# PM_Controller_v1p02.net
KiCad netlist of a schematic drawn in EAGLE
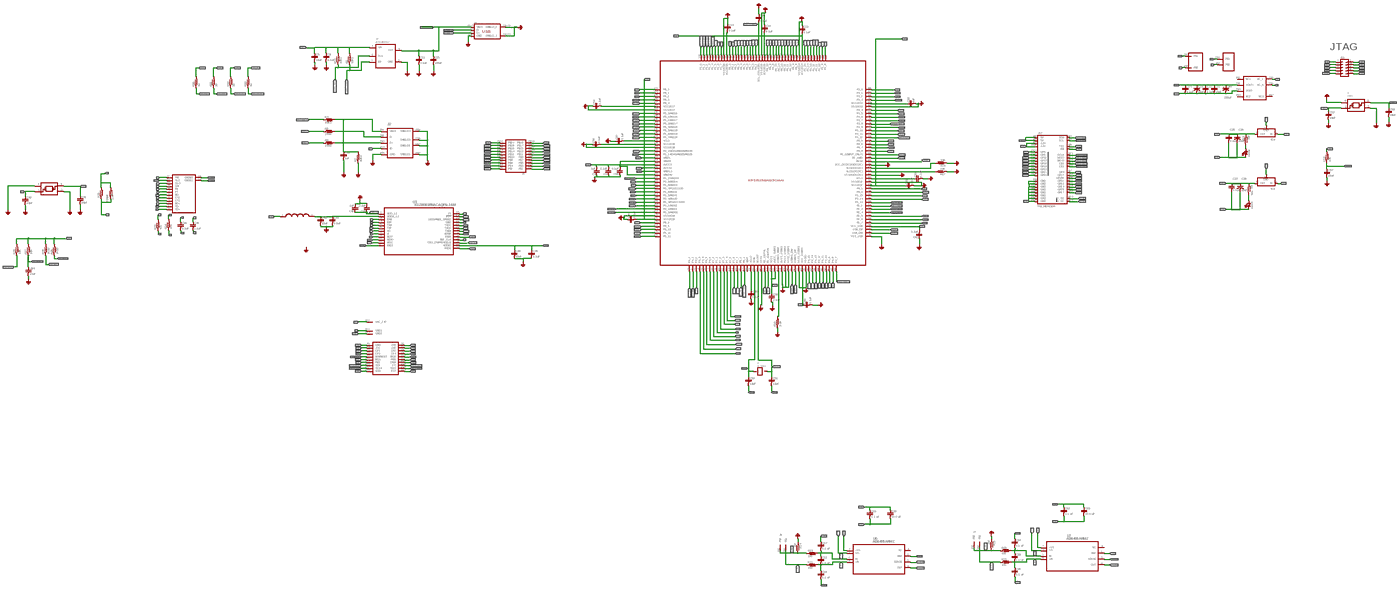
[diagram p0: schematic, sheet 1, overview]
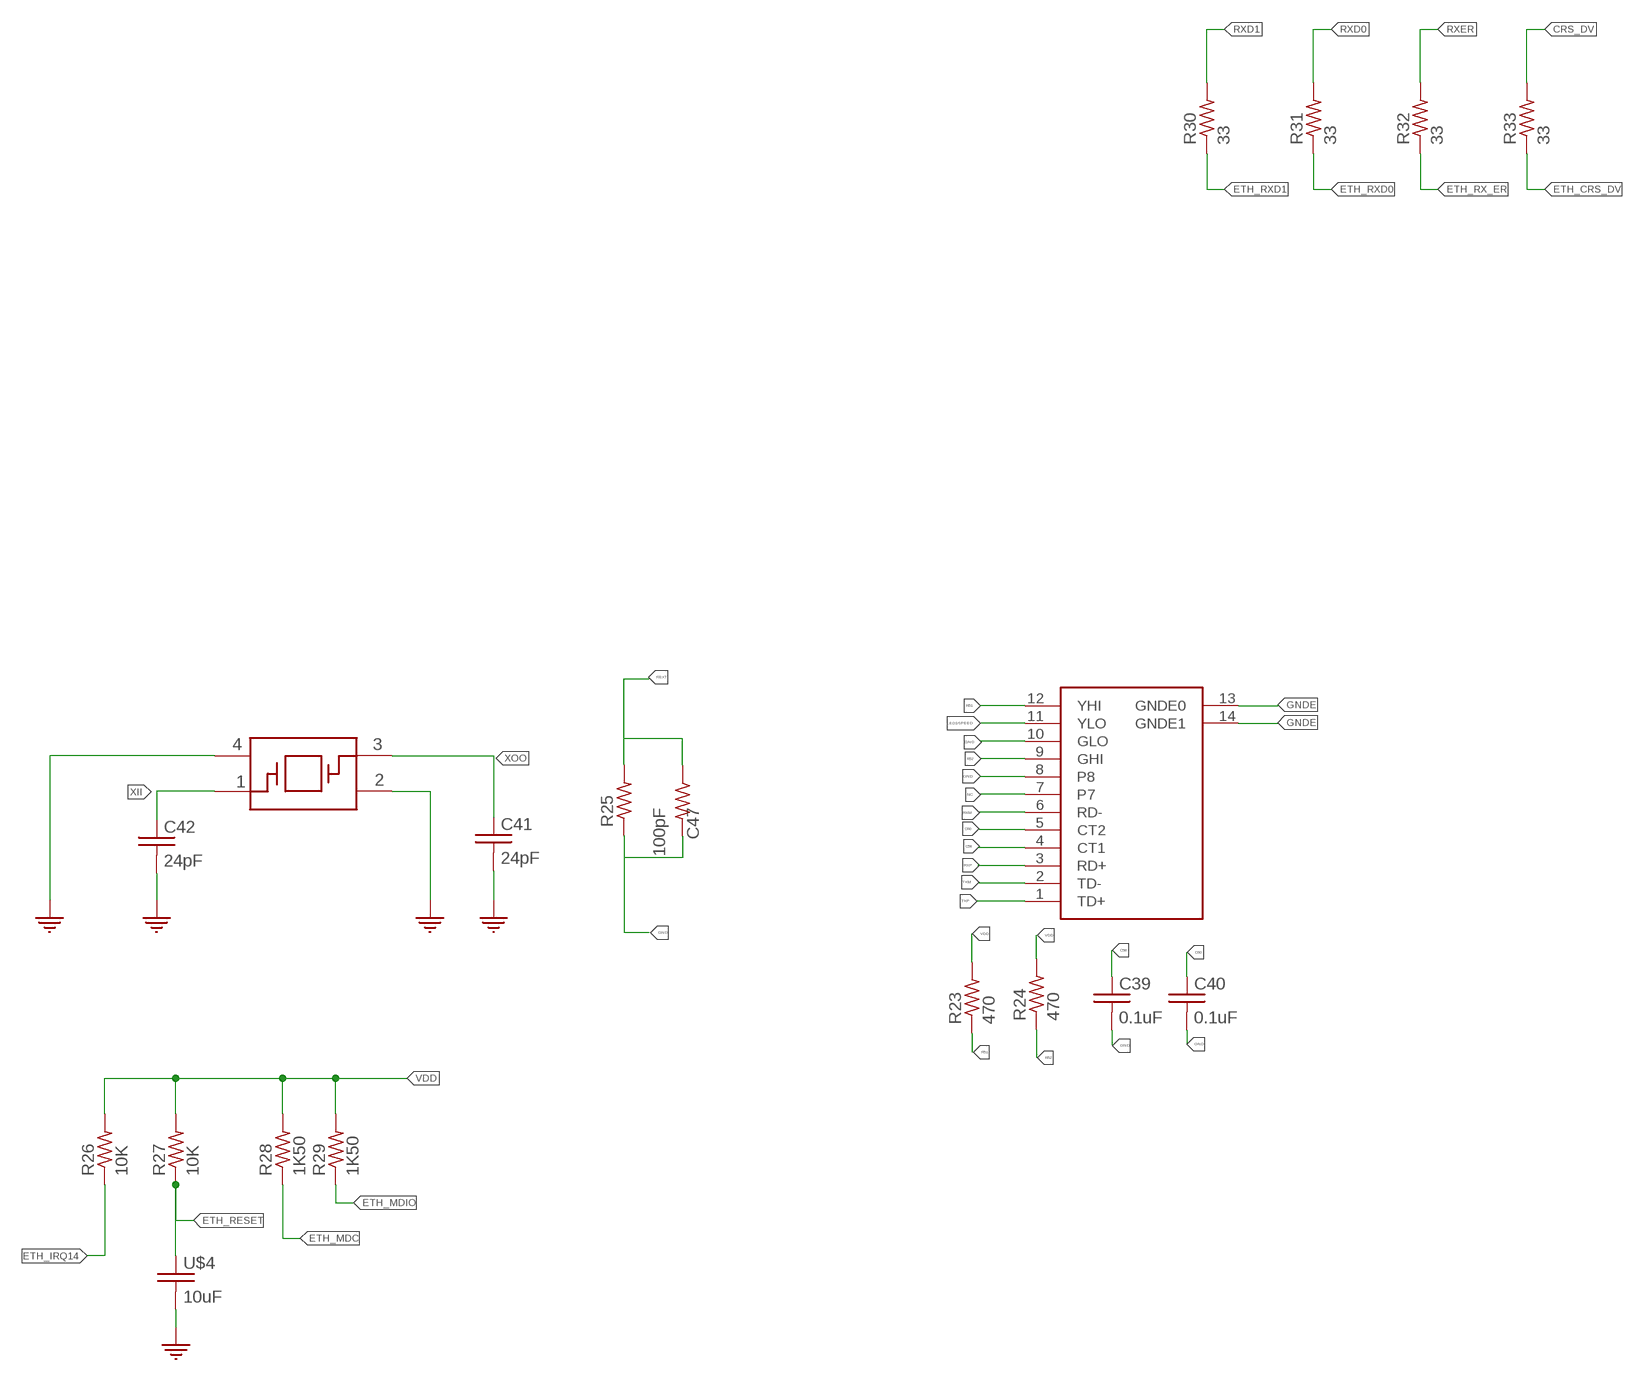
[diagram p1: schematic, sheet 1, part 1 of 6]
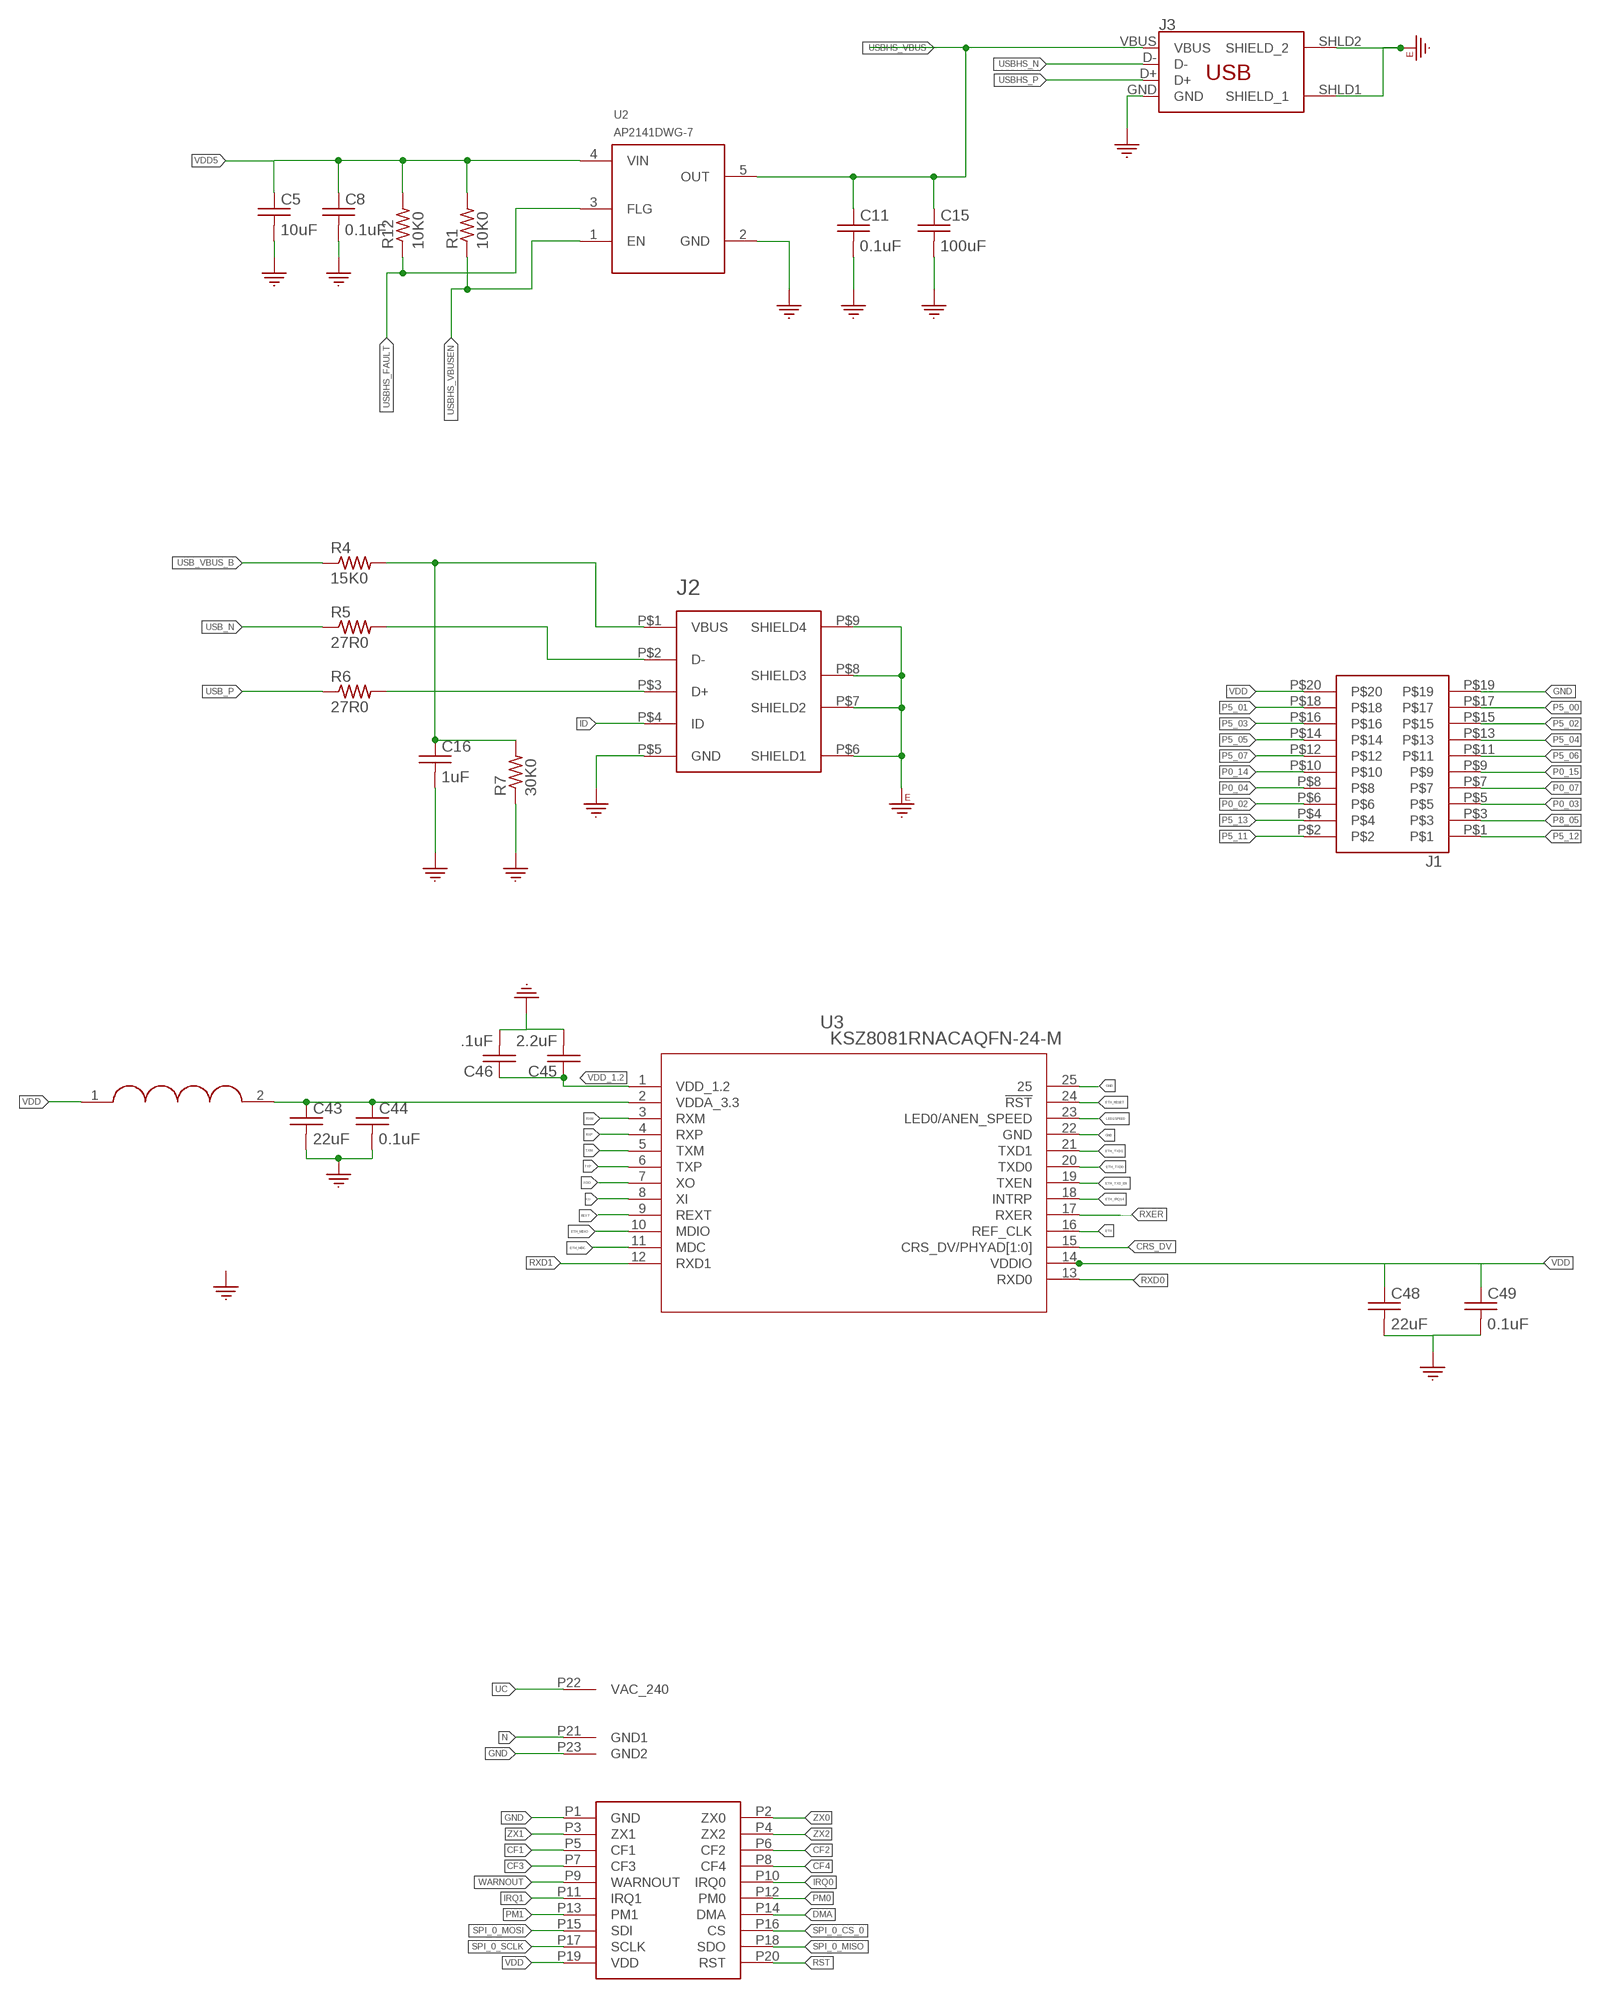
[diagram p2: schematic, sheet 1, part 2 of 6]
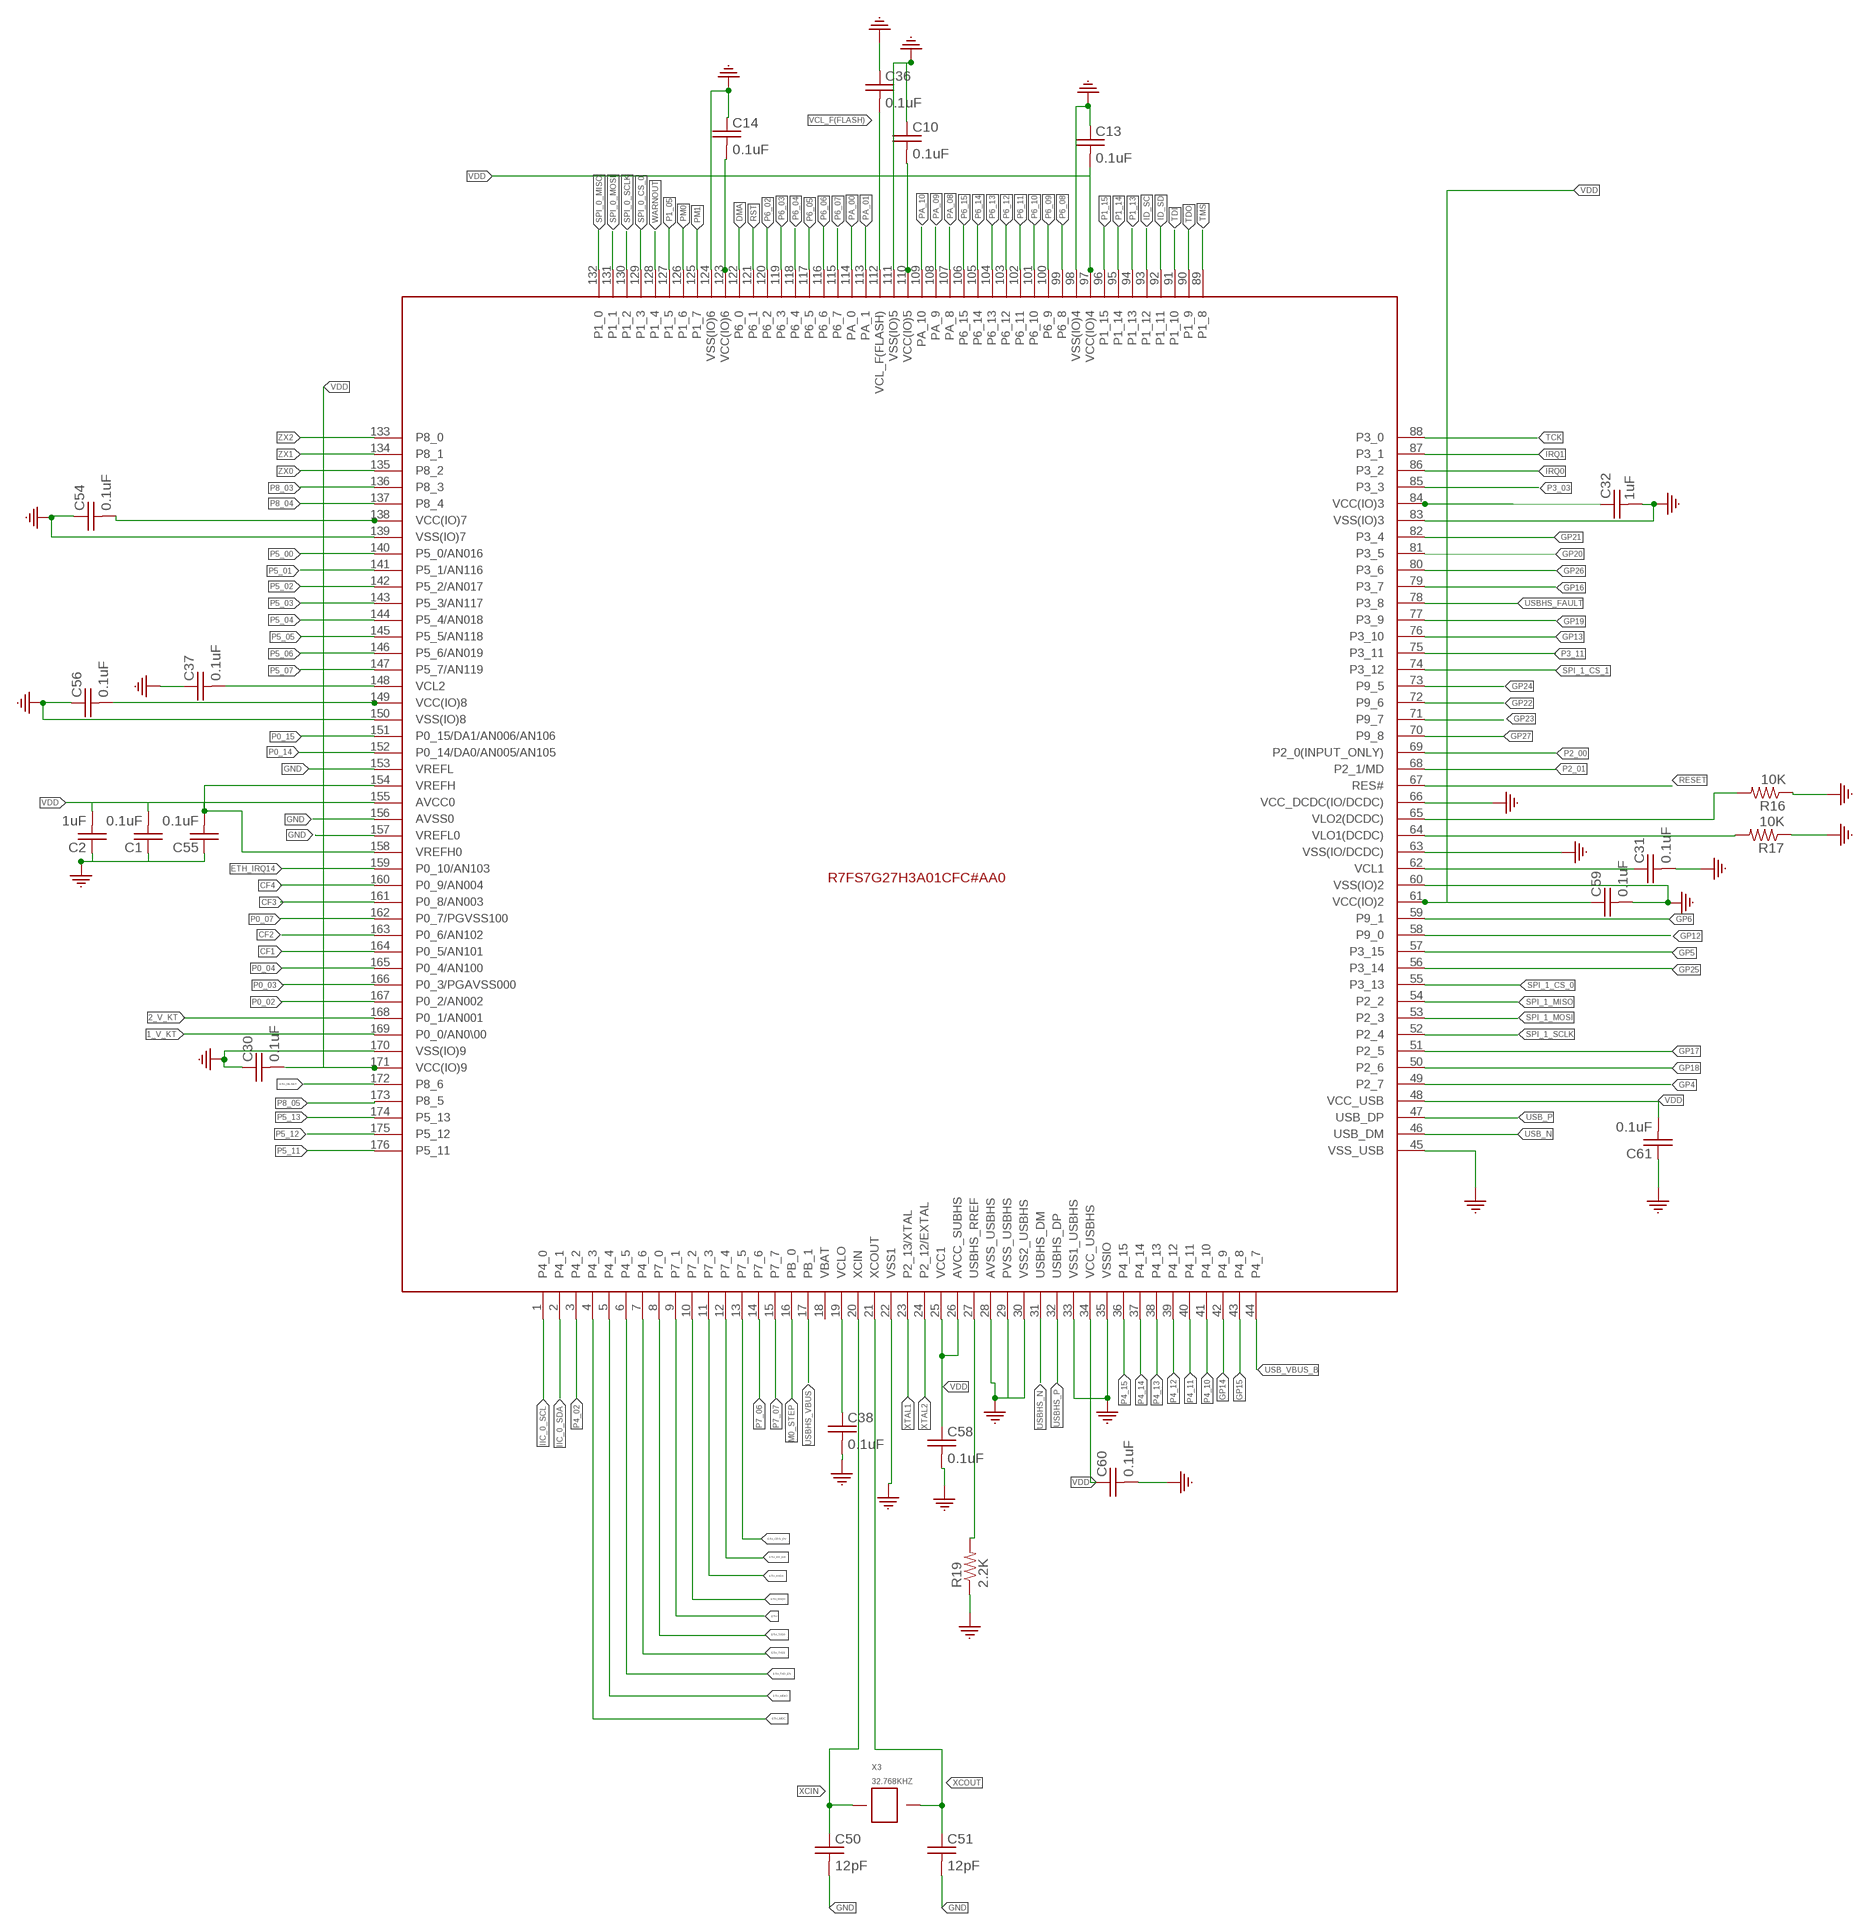
[diagram p3: schematic, sheet 1, part 3 of 6]
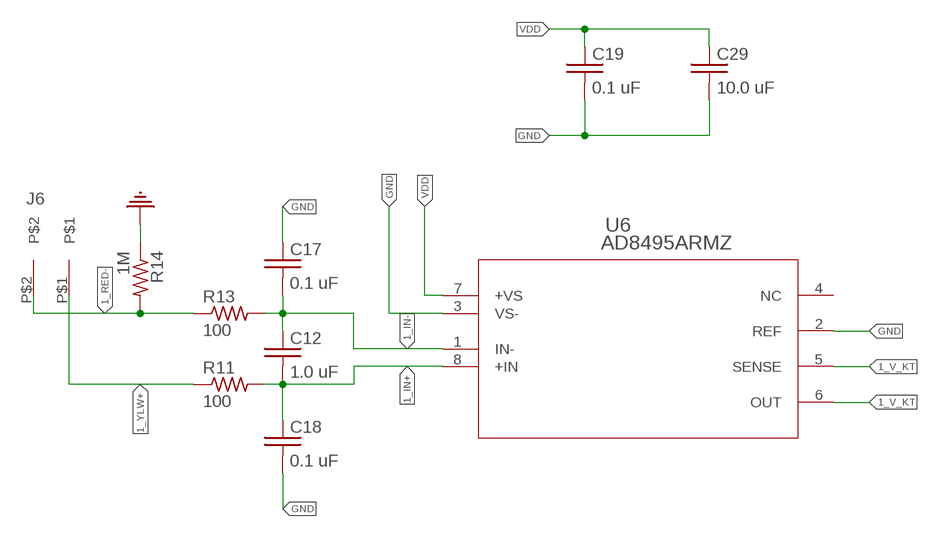
[diagram p4: schematic, sheet 1, part 4 of 6]
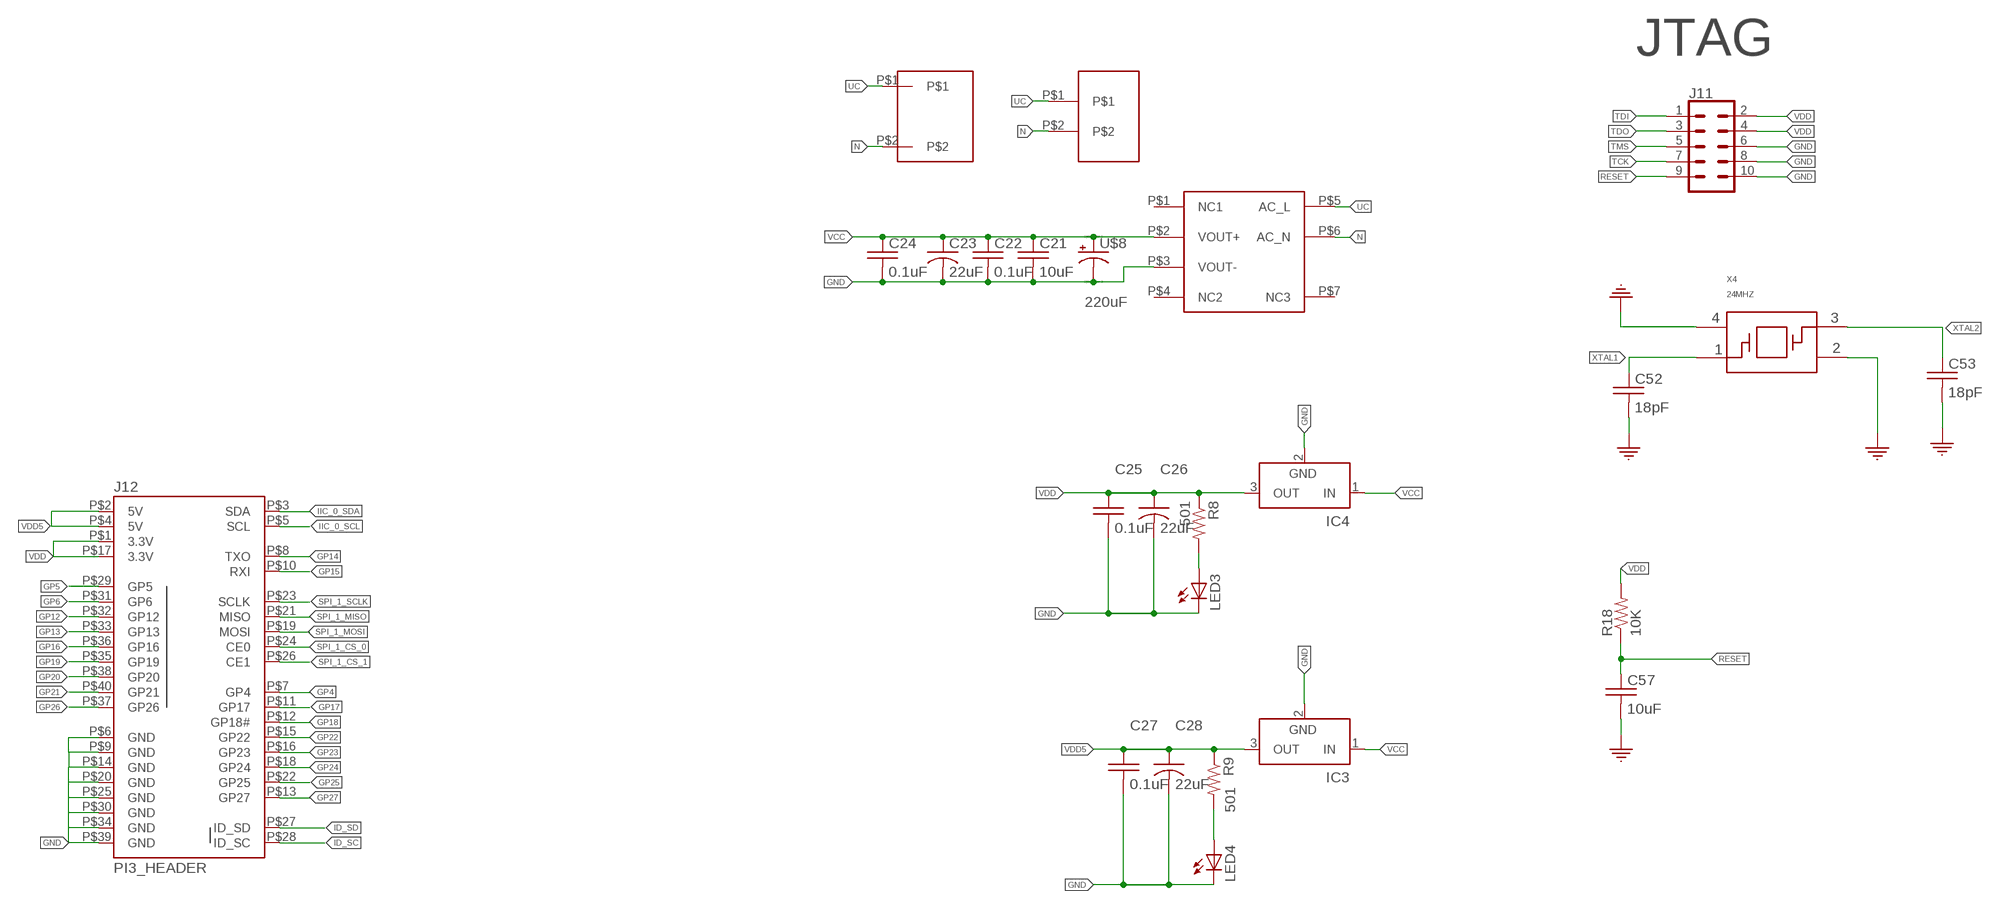
[diagram p5: schematic, sheet 1, part 5 of 6]
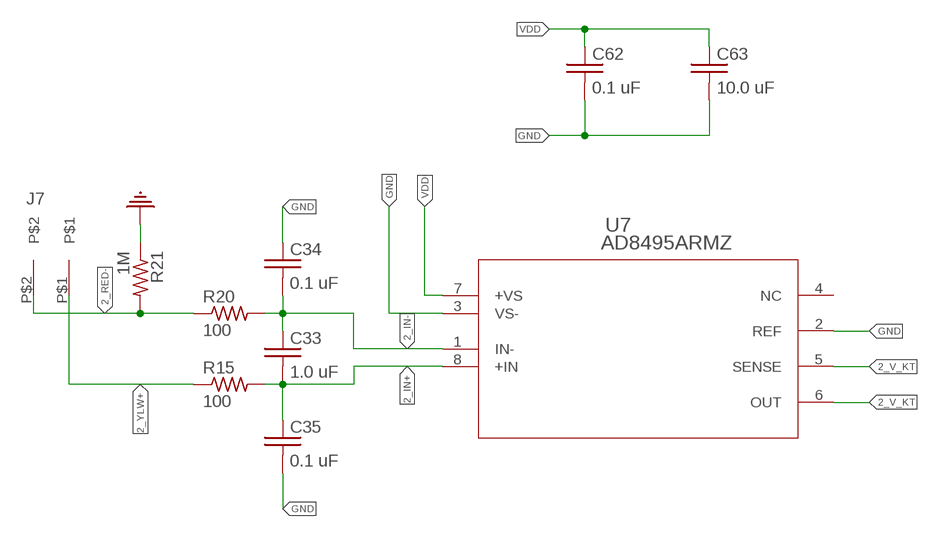
[diagram p6: schematic, sheet 1, part 6 of 6]

(export (version "E")
  (design (tool "Eeschema 10.0.6"))
  (components
    (comp (ref "C1")
      (value "0.1uF")
      (footprint "eagle-import:0402")
      (libsource (lib "eagle-import") (part "C_0402"))
    )
    (comp (ref "C2")
      (value "1uF")
      (footprint "eagle-import:0402")
      (libsource (lib "eagle-import") (part "C_0402"))
    )
    (comp (ref "C5")
      (value "10uF")
      (footprint "eagle-import:0402")
      (libsource (lib "eagle-import") (part "C_0402"))
    )
    (comp (ref "C8")
      (value "0.1uF")
      (footprint "eagle-import:0402")
      (libsource (lib "eagle-import") (part "C_0402"))
    )
    (comp (ref "C10")
      (value "0.1uF")
      (footprint "eagle-import:0402")
      (libsource (lib "eagle-import") (part "C_0402"))
    )
    (comp (ref "C11")
      (value "0.1uF")
      (footprint "eagle-import:0402")
      (libsource (lib "eagle-import") (part "C_0402"))
    )
    (comp (ref "C12")
      (value "1.0 uF")
      (footprint "eagle-import:0402")
      (libsource (lib "eagle-import") (part "C_0402"))
    )
    (comp (ref "C13")
      (value "0.1uF")
      (footprint "eagle-import:0402")
      (libsource (lib "eagle-import") (part "C_0402"))
    )
    (comp (ref "C14")
      (value "0.1uF")
      (footprint "eagle-import:0402")
      (libsource (lib "eagle-import") (part "C_0402"))
    )
    (comp (ref "C15")
      (value "100uF")
      (footprint "eagle-import:C1210")
      (libsource (lib "eagle-import") (part "C_1210"))
    )
    (comp (ref "C16")
      (value "1uF")
      (footprint "eagle-import:0402")
      (libsource (lib "eagle-import") (part "C_0402"))
    )
    (comp (ref "C17")
      (value "0.1 uF")
      (footprint "eagle-import:0402")
      (libsource (lib "eagle-import") (part "C_0402"))
    )
    (comp (ref "C18")
      (value "0.1 uF")
      (footprint "eagle-import:0402")
      (libsource (lib "eagle-import") (part "C_0402"))
    )
    (comp (ref "C19")
      (value "0.1 uF")
      (footprint "eagle-import:0402")
      (libsource (lib "eagle-import") (part "C_0402"))
    )
    (comp (ref "C20")
      (value "CAP_THIN_FILM_TDK_32922CAP")
      (footprint "eagle-import:CAP_THIN_FILM_32922")
      (libsource (lib "eagle-import") (part "CAP_THIN_FILM_TDK_32922CAP"))
    )
    (comp (ref "C21")
      (value "10uF")
      (footprint "eagle-import:0402")
      (libsource (lib "eagle-import") (part "C_0402"))
    )
    (comp (ref "C22")
      (value "0.1uF")
      (footprint "eagle-import:0402")
      (libsource (lib "eagle-import") (part "C_0402"))
    )
    (comp (ref "C23")
      (value "22uF")
      (footprint "eagle-import:C1206")
      (libsource (lib "eagle-import") (part "C-USC1206"))
    )
    (comp (ref "C24")
      (value "0.1uF")
      (footprint "eagle-import:0402")
      (libsource (lib "eagle-import") (part "C_0402"))
    )
    (comp (ref "C25")
      (value "0.1uF")
      (footprint "eagle-import:0402")
      (libsource (lib "eagle-import") (part "C_0402"))
    )
    (comp (ref "C26")
      (value "22uF")
      (footprint "eagle-import:C1206")
      (libsource (lib "eagle-import") (part "C-USC1206"))
    )
    (comp (ref "C27")
      (value "0.1uF")
      (footprint "eagle-import:0402")
      (libsource (lib "eagle-import") (part "C_0402"))
    )
    (comp (ref "C28")
      (value "22uF")
      (footprint "eagle-import:C1206")
      (libsource (lib "eagle-import") (part "C-USC1206"))
    )
    (comp (ref "C29")
      (value "10.0 uF")
      (footprint "eagle-import:0402")
      (libsource (lib "eagle-import") (part "C_0402"))
    )
    (comp (ref "C30")
      (value "0.1uF")
      (footprint "eagle-import:0402")
      (libsource (lib "eagle-import") (part "C_0402"))
    )
    (comp (ref "C31")
      (value "0.1uF")
      (footprint "eagle-import:0402")
      (libsource (lib "eagle-import") (part "C_0402"))
    )
    (comp (ref "C32")
      (value "1uF")
      (footprint "eagle-import:0402")
      (libsource (lib "eagle-import") (part "C_0402"))
    )
    (comp (ref "C33")
      (value "1.0 uF")
      (footprint "eagle-import:0402")
      (libsource (lib "eagle-import") (part "C_0402"))
    )
    (comp (ref "C34")
      (value "0.1 uF")
      (footprint "eagle-import:0402")
      (libsource (lib "eagle-import") (part "C_0402"))
    )
    (comp (ref "C35")
      (value "0.1 uF")
      (footprint "eagle-import:0402")
      (libsource (lib "eagle-import") (part "C_0402"))
    )
    (comp (ref "C36")
      (value "0.1uF")
      (footprint "eagle-import:0402")
      (libsource (lib "eagle-import") (part "C_0402"))
    )
    (comp (ref "C37")
      (value "0.1uF")
      (footprint "eagle-import:0402")
      (libsource (lib "eagle-import") (part "C_0402"))
    )
    (comp (ref "C38")
      (value "0.1uF")
      (footprint "eagle-import:0402")
      (libsource (lib "eagle-import") (part "C_0402"))
    )
    (comp (ref "C39")
      (value "0.1uF")
      (footprint "eagle-import:0402")
      (libsource (lib "eagle-import") (part "C_0402"))
    )
    (comp (ref "C40")
      (value "0.1uF")
      (footprint "eagle-import:0402")
      (libsource (lib "eagle-import") (part "C_0402"))
    )
    (comp (ref "C41")
      (value "24pF")
      (footprint "eagle-import:0402")
      (libsource (lib "eagle-import") (part "C_0402"))
    )
    (comp (ref "C42")
      (value "24pF")
      (footprint "eagle-import:0402")
      (libsource (lib "eagle-import") (part "C_0402"))
    )
    (comp (ref "C43")
      (value "22uF")
      (footprint "eagle-import:0603")
      (libsource (lib "eagle-import") (part "C_0603"))
    )
    (comp (ref "C44")
      (value "0.1uF")
      (footprint "eagle-import:0402")
      (libsource (lib "eagle-import") (part "C_0402"))
    )
    (comp (ref "C45")
      (value "2.2uF")
      (footprint "eagle-import:0402")
      (libsource (lib "eagle-import") (part "C_0402"))
    )
    (comp (ref "C46")
      (value ".1uF")
      (footprint "eagle-import:0402")
      (libsource (lib "eagle-import") (part "C_0402"))
    )
    (comp (ref "C47")
      (value "100pF")
      (footprint "eagle-import:0402")
      (libsource (lib "eagle-import") (part "R_0402"))
    )
    (comp (ref "C48")
      (value "22uF")
      (footprint "eagle-import:0603")
      (libsource (lib "eagle-import") (part "C_0603"))
    )
    (comp (ref "C49")
      (value "0.1uF")
      (footprint "eagle-import:0402")
      (libsource (lib "eagle-import") (part "C_0402"))
    )
    (comp (ref "C50")
      (value "12pF")
      (footprint "eagle-import:0402")
      (libsource (lib "eagle-import") (part "C_0402"))
    )
    (comp (ref "C51")
      (value "12pF")
      (footprint "eagle-import:0402")
      (libsource (lib "eagle-import") (part "C_0402"))
    )
    (comp (ref "C52")
      (value "18pF")
      (footprint "eagle-import:0402")
      (libsource (lib "eagle-import") (part "C_0402"))
    )
    (comp (ref "C53")
      (value "18pF")
      (footprint "eagle-import:0402")
      (libsource (lib "eagle-import") (part "C_0402"))
    )
    (comp (ref "C54")
      (value "0.1uF")
      (footprint "eagle-import:0402")
      (libsource (lib "eagle-import") (part "C_0402"))
    )
    (comp (ref "C55")
      (value "0.1uF")
      (footprint "eagle-import:0402")
      (libsource (lib "eagle-import") (part "C_0402"))
    )
    (comp (ref "C56")
      (value "0.1uF")
      (footprint "eagle-import:0402")
      (libsource (lib "eagle-import") (part "C_0402"))
    )
    (comp (ref "C57")
      (value "10uF")
      (footprint "eagle-import:0402")
      (libsource (lib "eagle-import") (part "C_0402"))
    )
    (comp (ref "C58")
      (value "0.1uF")
      (footprint "eagle-import:0402")
      (libsource (lib "eagle-import") (part "C_0402"))
    )
    (comp (ref "C59")
      (value "0.1uF")
      (footprint "eagle-import:0402")
      (libsource (lib "eagle-import") (part "C_0402"))
    )
    (comp (ref "C60")
      (value "0.1uF")
      (footprint "eagle-import:0402")
      (libsource (lib "eagle-import") (part "C_0402"))
    )
    (comp (ref "C61")
      (value "0.1uF")
      (footprint "eagle-import:0402")
      (libsource (lib "eagle-import") (part "C_0402"))
    )
    (comp (ref "C62")
      (value "0.1 uF")
      (footprint "eagle-import:0402")
      (libsource (lib "eagle-import") (part "C_0402"))
    )
    (comp (ref "C63")
      (value "10.0 uF")
      (footprint "eagle-import:0402")
      (libsource (lib "eagle-import") (part "C_0402"))
    )
    (comp (ref "FB2/2")
      (value "FB_0805_120_OHM")
      (footprint "eagle-import:0805")
      (libsource (lib "eagle-import") (part "FB_0805_120_OHM"))
    )
    (comp (ref "IC3")
      (value "LT1129CST5")
      (footprint "eagle-import:SOT223")
      (fields (field (name "MPN") "LT1129CST-5#PBF"))
      (libsource (lib "eagle-import") (part "LT1129CST5"))
    )
    (comp (ref "IC4")
      (value "LT1129CST3")
      (footprint "eagle-import:SOT223")
      (fields (field (name "MPN") "LT1129CST-5#PBF"))
      (libsource (lib "eagle-import") (part "LT1129CST3"))
    )
    (comp (ref "J1")
      (value "2_X_10_HEADER_GENERIC")
      (footprint "eagle-import:2_X_10_.1_INCH")
      (libsource (lib "eagle-import") (part "2_X_10_HEADER_GENERIC"))
    )
    (comp (ref "J2")
      (value "USB_MICRO-B")
      (footprint "eagle-import:USB_MICRO-B")
      (libsource (lib "eagle-import") (part "USB_MICRO-B"))
    )
    (comp (ref "J3")
      (value "USB_A")
      (footprint "eagle-import:USB_A_SMT")
      (libsource (lib "eagle-import") (part "USB_A"))
    )
    (comp (ref "J4")
      (value "RJ45_WITH_ELEC")
      (footprint "eagle-import:RJ45_TH_ELEC")
      (libsource (lib "eagle-import") (part "RJ45_WITH_ELEC"))
    )
    (comp (ref "J6")
      (value "3.81MM_1_X_2_RT_ANGLE_PLUG_HEADER")
      (footprint "eagle-import:2_3.81MM_PITCH")
      (libsource (lib "eagle-import") (part "3.81MM_1_X_2_RT_ANGLE_PLUG_HEADER"))
    )
    (comp (ref "J7")
      (value "3.81MM_1_X_2_RT_ANGLE_PLUG_HEADER")
      (footprint "eagle-import:2_3.81MM_PITCH")
      (libsource (lib "eagle-import") (part "3.81MM_1_X_2_RT_ANGLE_PLUG_HEADER"))
    )
    (comp (ref "J11")
      (value "CONN_05X2PTH")
      (footprint "eagle-import:2X5")
      (libsource (lib "eagle-import") (part "CONN_05X2PTH"))
    )
    (comp (ref "J12")
      (value "PI3_HEADER")
      (footprint "eagle-import:HEADER_2_X_20_.1_INCH")
      (libsource (lib "eagle-import") (part "PI3_HEADER"))
    )
    (comp (ref "LED3")
      (value "LED_0805_GREEN")
      (footprint "eagle-import:LED_0805_GREEN")
      (libsource (lib "eagle-import") (part "LED_0805_GREEN"))
    )
    (comp (ref "LED4")
      (value "LED_0805_GREEN")
      (footprint "eagle-import:LED_0805_GREEN")
      (libsource (lib "eagle-import") (part "LED_0805_GREEN"))
    )
    (comp (ref "R1")
      (value "10K0")
      (footprint "eagle-import:0402")
      (libsource (lib "eagle-import") (part "R_0402"))
    )
    (comp (ref "R4")
      (value "15K0")
      (footprint "eagle-import:0402")
      (libsource (lib "eagle-import") (part "R_0402"))
    )
    (comp (ref "R5")
      (value "27R0")
      (footprint "eagle-import:0402")
      (libsource (lib "eagle-import") (part "R_0402"))
    )
    (comp (ref "R6")
      (value "27R0")
      (footprint "eagle-import:0402")
      (libsource (lib "eagle-import") (part "R_0402"))
    )
    (comp (ref "R7")
      (value "30K0")
      (footprint "eagle-import:0402")
      (libsource (lib "eagle-import") (part "R_0402"))
    )
    (comp (ref "R8")
      (value "501")
      (footprint "eagle-import:0402")
      (libsource (lib "eagle-import") (part "R_0402"))
    )
    (comp (ref "R9")
      (value "501")
      (footprint "eagle-import:0402")
      (libsource (lib "eagle-import") (part "R_0402"))
    )
    (comp (ref "R11")
      (value "100")
      (footprint "eagle-import:0402")
      (libsource (lib "eagle-import") (part "R_0402"))
    )
    (comp (ref "R12")
      (value "10K0")
      (footprint "eagle-import:0402")
      (libsource (lib "eagle-import") (part "R_0402"))
    )
    (comp (ref "R13")
      (value "100")
      (footprint "eagle-import:0402")
      (libsource (lib "eagle-import") (part "R_0402"))
    )
    (comp (ref "R14")
      (value "1M")
      (footprint "eagle-import:0402")
      (libsource (lib "eagle-import") (part "R_0402"))
    )
    (comp (ref "R15")
      (value "100")
      (footprint "eagle-import:0402")
      (libsource (lib "eagle-import") (part "R_0402"))
    )
    (comp (ref "R16")
      (value "10K")
      (footprint "eagle-import:0402")
      (libsource (lib "eagle-import") (part "R_0402"))
    )
    (comp (ref "R17")
      (value "10K")
      (footprint "eagle-import:0402")
      (libsource (lib "eagle-import") (part "R_0402"))
    )
    (comp (ref "R18")
      (value "10K")
      (footprint "eagle-import:0402")
      (libsource (lib "eagle-import") (part "R_0402"))
    )
    (comp (ref "R19")
      (value "2.2K")
      (footprint "eagle-import:0402")
      (libsource (lib "eagle-import") (part "R_0402"))
    )
    (comp (ref "R20")
      (value "100")
      (footprint "eagle-import:0402")
      (libsource (lib "eagle-import") (part "R_0402"))
    )
    (comp (ref "R21")
      (value "1M")
      (footprint "eagle-import:0402")
      (libsource (lib "eagle-import") (part "R_0402"))
    )
    (comp (ref "R23")
      (value "470")
      (footprint "eagle-import:0402")
      (libsource (lib "eagle-import") (part "R_0402"))
    )
    (comp (ref "R24")
      (value "470")
      (footprint "eagle-import:0402")
      (libsource (lib "eagle-import") (part "R_0402"))
    )
    (comp (ref "R25")
      (value "6k49")
      (footprint "eagle-import:0402")
      (libsource (lib "eagle-import") (part "R_0402"))
    )
    (comp (ref "R26")
      (value "10K")
      (footprint "eagle-import:0402")
      (libsource (lib "eagle-import") (part "R_0402"))
    )
    (comp (ref "R27")
      (value "10K")
      (footprint "eagle-import:0402")
      (libsource (lib "eagle-import") (part "R_0402"))
    )
    (comp (ref "R28")
      (value "1K50")
      (footprint "eagle-import:0402")
      (libsource (lib "eagle-import") (part "R_0402"))
    )
    (comp (ref "R29")
      (value "1K50")
      (footprint "eagle-import:0402")
      (libsource (lib "eagle-import") (part "R_0402"))
    )
    (comp (ref "R30")
      (value "33")
      (footprint "eagle-import:0402")
      (libsource (lib "eagle-import") (part "R_0402"))
    )
    (comp (ref "R31")
      (value "33")
      (footprint "eagle-import:0402")
      (libsource (lib "eagle-import") (part "R_0402"))
    )
    (comp (ref "R32")
      (value "33")
      (footprint "eagle-import:0402")
      (libsource (lib "eagle-import") (part "R_0402"))
    )
    (comp (ref "R33")
      (value "33")
      (footprint "eagle-import:0402")
      (libsource (lib "eagle-import") (part "R_0402"))
    )
    (comp (ref "U$2")
      (value "METER_BASE")
      (footprint "eagle-import:METER_BASE")
      (libsource (lib "eagle-import") (part "METER_BASE"))
    )
    (comp (ref "U$3")
      (value "XTAL_25_MHZ")
      (footprint "eagle-import:SMD_3225")
      (libsource (lib "eagle-import") (part "XTAL_25_MHZ"))
    )
    (comp (ref "U$4")
      (value "10uF")
      (footprint "eagle-import:0402")
      (libsource (lib "eagle-import") (part "C_0402"))
    )
    (comp (ref "U$7")
      (value "VAR_10MM_VDRUS10")
      (footprint "eagle-import:VAR_10MM_VDRUS10")
      (libsource (lib "eagle-import") (part "VAR_10MM_VDRUS10"))
    )
    (comp (ref "U$8")
      (value "220uF")
      (footprint "eagle-import:C_AL_ELECTROLYTIC_SMD_220UF")
      (libsource (lib "eagle-import") (part "C_AL_ELECTROLYTIC_SMD_220UF"))
    )
    (comp (ref "U2")
      (value "AP2141DWG-5")
      (footprint "eagle-import:SOT-23-5")
      (libsource (lib "eagle-import") (part "AP2141DWG-5"))
    )
    (comp (ref "U3")
      (value "KSZ8081RNACAQFN-24-M")
      (footprint "eagle-import:QFN-24-M")
      (fields (field (name "MANUFACTURER_PART_NUMBER") "KSZ8081RNACA"))
      (libsource (lib "eagle-import") (part "KSZ8081RNACAQFN-24-M"))
    )
    (comp (ref "U4")
      (value "S7G2_X_176")
      (footprint "eagle-import:LQFP176_24X24")
      (libsource (lib "eagle-import") (part "S7G2_X_176"))
    )
    (comp (ref "U5")
      (value "TMLM_04109")
      (footprint "eagle-import:TMLM04")
      (libsource (lib "eagle-import") (part "TMLM_04109"))
    )
    (comp (ref "U6")
      (value "AD8495ARMZ")
      (footprint "eagle-import:RM_8_ADI")
      (libsource (lib "eagle-import") (part "AD8495ARMZ"))
    )
    (comp (ref "U7")
      (value "AD8495ARMZ")
      (footprint "eagle-import:RM_8_ADI")
      (libsource (lib "eagle-import") (part "AD8495ARMZ"))
    )
    (comp (ref "X3")
      (value "32.768KHZ")
      (footprint "eagle-import:SMD_X_2_PADS")
      (libsource (lib "eagle-import") (part "XTAL_32.768KHZ"))
    )
    (comp (ref "X4")
      (value "24MHZ")
      (footprint "eagle-import:SMD_3225")
      (libsource (lib "eagle-import") (part "XTAL_24_MHZ"))
    )
  )
  (nets
    (net (code "1") (name "1_IN+") (class "Default")
      (node (ref "C12") (pin "P$2") (pinfunction "2_P$2") (pintype "passive"))
      (node (ref "C18") (pin "P$1") (pinfunction "1_P$1") (pintype "passive"))
      (node (ref "R11") (pin "P$2") (pinfunction "2_P$2") (pintype "passive"))
      (node (ref "U6") (pin "8") (pinfunction "+IN_8") (pintype "input"))
    )
    (net (code "2") (name "1_IN-") (class "Default")
      (node (ref "C12") (pin "P$1") (pinfunction "1_P$1") (pintype "passive"))
      (node (ref "C17") (pin "P$2") (pinfunction "2_P$2") (pintype "passive"))
      (node (ref "R13") (pin "P$2") (pinfunction "2_P$2") (pintype "passive"))
      (node (ref "U6") (pin "1") (pinfunction "IN-_1") (pintype "input"))
    )
    (net (code "3") (name "1_RED-") (class "Default")
      (node (ref "J6") (pin "P$2") (pinfunction "P$2_P$2") (pintype "bidirectional"))
      (node (ref "R13") (pin "P$1") (pinfunction "1_P$1") (pintype "passive"))
      (node (ref "R14") (pin "P$2") (pinfunction "2_P$2") (pintype "passive"))
    )
    (net (code "4") (name "1_V_KT") (class "Default")
      (node (ref "U4") (pin "169") (pinfunction "P0_0/AN0\\00_169") (pintype "bidirectional"))
      (node (ref "U6") (pin "5") (pinfunction "SENSE_5") (pintype "passive"))
      (node (ref "U6") (pin "6") (pinfunction "OUT_6") (pintype "output"))
    )
    (net (code "5") (name "1_YLW+") (class "Default")
      (node (ref "J6") (pin "P$1") (pinfunction "P$1_P$1") (pintype "bidirectional"))
      (node (ref "R11") (pin "P$1") (pinfunction "1_P$1") (pintype "passive"))
    )
    (net (code "6") (name "2_IN+") (class "Default")
      (node (ref "C33") (pin "P$2") (pinfunction "2_P$2") (pintype "passive"))
      (node (ref "C35") (pin "P$1") (pinfunction "1_P$1") (pintype "passive"))
      (node (ref "R15") (pin "P$2") (pinfunction "2_P$2") (pintype "passive"))
      (node (ref "U7") (pin "8") (pinfunction "+IN_8") (pintype "input"))
    )
    (net (code "7") (name "2_IN-") (class "Default")
      (node (ref "C33") (pin "P$1") (pinfunction "1_P$1") (pintype "passive"))
      (node (ref "C34") (pin "P$2") (pinfunction "2_P$2") (pintype "passive"))
      (node (ref "R20") (pin "P$2") (pinfunction "2_P$2") (pintype "passive"))
      (node (ref "U7") (pin "1") (pinfunction "IN-_1") (pintype "input"))
    )
    (net (code "8") (name "2_RED-") (class "Default")
      (node (ref "J7") (pin "P$2") (pinfunction "P$2_P$2") (pintype "bidirectional"))
      (node (ref "R20") (pin "P$1") (pinfunction "1_P$1") (pintype "passive"))
      (node (ref "R21") (pin "P$2") (pinfunction "2_P$2") (pintype "passive"))
    )
    (net (code "9") (name "2_V_KT") (class "Default")
      (node (ref "U4") (pin "168") (pinfunction "P0_1/AN001_168") (pintype "bidirectional"))
      (node (ref "U7") (pin "5") (pinfunction "SENSE_5") (pintype "passive"))
      (node (ref "U7") (pin "6") (pinfunction "OUT_6") (pintype "output"))
    )
    (net (code "10") (name "2_YLW+") (class "Default")
      (node (ref "J7") (pin "P$1") (pinfunction "P$1_P$1") (pintype "bidirectional"))
      (node (ref "R15") (pin "P$1") (pinfunction "1_P$1") (pintype "passive"))
    )
    (net (code "11") (name "C58") (class "Default")
      (node (ref "C39") (pin "P$1") (pinfunction "1_P$1") (pintype "passive"))
      (node (ref "J4") (pin "4") (pinfunction "CT1_4") (pintype "bidirectional"))
    )
    (net (code "12") (name "C60") (class "Default")
      (node (ref "C40") (pin "P$1") (pinfunction "1_P$1") (pintype "passive"))
      (node (ref "J4") (pin "5") (pinfunction "CT2_5") (pintype "bidirectional"))
    )
    (net (code "13") (name "CF1") (class "Default")
      (node (ref "U$2") (pin "P5") (pinfunction "CF1_P5") (pintype "bidirectional"))
      (node (ref "U4") (pin "164") (pinfunction "P0_5/AN101_164") (pintype "bidirectional"))
    )
    (net (code "14") (name "CF2") (class "Default")
      (node (ref "U$2") (pin "P6") (pinfunction "CF2_P6") (pintype "bidirectional"))
      (node (ref "U4") (pin "163") (pinfunction "P0_6/AN102_163") (pintype "bidirectional"))
    )
    (net (code "15") (name "CF3") (class "Default")
      (node (ref "U$2") (pin "P7") (pinfunction "CF3_P7") (pintype "bidirectional"))
      (node (ref "U4") (pin "161") (pinfunction "P0_8/AN003_161") (pintype "bidirectional"))
    )
    (net (code "16") (name "CF4") (class "Default")
      (node (ref "U$2") (pin "P8") (pinfunction "CF4_P8") (pintype "bidirectional"))
      (node (ref "U4") (pin "160") (pinfunction "P0_9/AN004_160") (pintype "bidirectional"))
    )
    (net (code "17") (name "CRS_DV") (class "Default")
      (node (ref "R33") (pin "P$2") (pinfunction "2_P$2") (pintype "passive"))
      (node (ref "U3") (pin "15") (pinfunction "CRS_DV/PHYAD[1:0]_15") (pintype "bidirectional"))
    )
    (net (code "18") (name "DMA") (class "Default")
      (node (ref "U$2") (pin "P14") (pinfunction "DMA_P14") (pintype "bidirectional"))
      (node (ref "U4") (pin "122") (pinfunction "P6_0_122") (pintype "bidirectional"))
    )
    (net (code "19") (name "ETH") (class "Default")
      (node (ref "U3") (pin "16") (pinfunction "REF_CLK_16") (pintype "bidirectional"))
      (node (ref "U4") (pin "9") (pinfunction "P7_1_9") (pintype "bidirectional"))
    )
    (net (code "20") (name "ETH_CRS_DV") (class "Default")
      (node (ref "R33") (pin "P$1") (pinfunction "1_P$1") (pintype "passive"))
      (node (ref "U4") (pin "13") (pinfunction "P7_5_13") (pintype "bidirectional"))
    )
    (net (code "21") (name "ETH_IRQ14") (class "Default")
      (node (ref "R26") (pin "P$1") (pinfunction "1_P$1") (pintype "passive"))
      (node (ref "U3") (pin "18") (pinfunction "INTRP_18") (pintype "bidirectional"))
      (node (ref "U4") (pin "159") (pinfunction "P0_10/AN103_159") (pintype "bidirectional"))
    )
    (net (code "22") (name "ETH_MDC") (class "Default")
      (node (ref "R28") (pin "P$1") (pinfunction "1_P$1") (pintype "passive"))
      (node (ref "U3") (pin "11") (pinfunction "MDC_11") (pintype "input"))
      (node (ref "U4") (pin "4") (pinfunction "P4_3_4") (pintype "bidirectional"))
    )
    (net (code "23") (name "ETH_MDIO") (class "Default")
      (node (ref "R29") (pin "P$1") (pinfunction "1_P$1") (pintype "passive"))
      (node (ref "U3") (pin "10") (pinfunction "MDIO_10") (pintype "bidirectional"))
      (node (ref "U4") (pin "5") (pinfunction "P4_4_5") (pintype "bidirectional"))
    )
    (net (code "24") (name "ETH_RESET") (class "Default")
      (node (ref "R27") (pin "P$1") (pinfunction "1_P$1") (pintype "passive"))
      (node (ref "U$4") (pin "P$1") (pinfunction "1_P$1") (pintype "passive"))
      (node (ref "U3") (pin "24") (pinfunction "~{RST}_24") (pintype "input"))
      (node (ref "U4") (pin "172") (pinfunction "P8_6_172") (pintype "bidirectional"))
    )
    (net (code "25") (name "ETH_RXD0") (class "Default")
      (node (ref "R31") (pin "P$1") (pinfunction "1_P$1") (pintype "passive"))
      (node (ref "U4") (pin "10") (pinfunction "P7_2_10") (pintype "bidirectional"))
    )
    (net (code "26") (name "ETH_RXD1") (class "Default")
      (node (ref "R30") (pin "P$1") (pinfunction "1_P$1") (pintype "passive"))
      (node (ref "U4") (pin "11") (pinfunction "P7_3_11") (pintype "bidirectional"))
    )
    (net (code "27") (name "ETH_RX_ER") (class "Default")
      (node (ref "R32") (pin "P$1") (pinfunction "1_P$1") (pintype "passive"))
      (node (ref "U4") (pin "12") (pinfunction "P7_4_12") (pintype "bidirectional"))
    )
    (net (code "28") (name "ETH_TXD0") (class "Default")
      (node (ref "U3") (pin "20") (pinfunction "TXD0_20") (pintype "input"))
      (node (ref "U4") (pin "8") (pinfunction "P7_0_8") (pintype "bidirectional"))
    )
    (net (code "29") (name "ETH_TXD1") (class "Default")
      (node (ref "U3") (pin "21") (pinfunction "TXD1_21") (pintype "bidirectional"))
      (node (ref "U4") (pin "7") (pinfunction "P4_6_7") (pintype "bidirectional"))
    )
    (net (code "30") (name "ETH_TXD_EN") (class "Default")
      (node (ref "U3") (pin "19") (pinfunction "TXEN_19") (pintype "input"))
      (node (ref "U4") (pin "6") (pinfunction "P4_5_6") (pintype "bidirectional"))
    )
    (net (code "31") (name "GND") (class "Default")
      (node (ref "C1") (pin "P$1") (pinfunction "1_P$1") (pintype "passive"))
      (node (ref "C10") (pin "P$1") (pinfunction "1_P$1") (pintype "passive"))
      (node (ref "C11") (pin "P$2") (pinfunction "2_P$2") (pintype "passive"))
      (node (ref "C13") (pin "P$1") (pinfunction "1_P$1") (pintype "passive"))
      (node (ref "C14") (pin "P$1") (pinfunction "1_P$1") (pintype "passive"))
      (node (ref "C15") (pin "2") (pinfunction "2_2") (pintype "passive"))
      (node (ref "C16") (pin "P$2") (pinfunction "2_P$2") (pintype "passive"))
      (node (ref "C17") (pin "P$1") (pinfunction "1_P$1") (pintype "passive"))
      (node (ref "C18") (pin "P$2") (pinfunction "2_P$2") (pintype "passive"))
      (node (ref "C19") (pin "P$2") (pinfunction "2_P$2") (pintype "passive"))
      (node (ref "C2") (pin "P$1") (pinfunction "1_P$1") (pintype "passive"))
      (node (ref "C21") (pin "P$2") (pinfunction "2_P$2") (pintype "passive"))
      (node (ref "C22") (pin "P$2") (pinfunction "2_P$2") (pintype "passive"))
      (node (ref "C23") (pin "2") (pinfunction "2_2") (pintype "passive"))
      (node (ref "C24") (pin "P$2") (pinfunction "2_P$2") (pintype "passive"))
      (node (ref "C25") (pin "P$2") (pinfunction "2_P$2") (pintype "passive"))
      (node (ref "C26") (pin "2") (pinfunction "2_2") (pintype "passive"))
      (node (ref "C27") (pin "P$2") (pinfunction "2_P$2") (pintype "passive"))
      (node (ref "C28") (pin "2") (pinfunction "2_2") (pintype "passive"))
      (node (ref "C29") (pin "P$2") (pinfunction "2_P$2") (pintype "passive"))
      (node (ref "C30") (pin "P$1") (pinfunction "1_P$1") (pintype "passive"))
      (node (ref "C31") (pin "P$2") (pinfunction "2_P$2") (pintype "passive"))
      (node (ref "C32") (pin "P$2") (pinfunction "2_P$2") (pintype "passive"))
      (node (ref "C34") (pin "P$1") (pinfunction "1_P$1") (pintype "passive"))
      (node (ref "C35") (pin "P$2") (pinfunction "2_P$2") (pintype "passive"))
      (node (ref "C36") (pin "P$1") (pinfunction "1_P$1") (pintype "passive"))
      (node (ref "C37") (pin "P$1") (pinfunction "1_P$1") (pintype "passive"))
      (node (ref "C38") (pin "P$2") (pinfunction "2_P$2") (pintype "passive"))
      (node (ref "C39") (pin "P$2") (pinfunction "2_P$2") (pintype "passive"))
      (node (ref "C40") (pin "P$2") (pinfunction "2_P$2") (pintype "passive"))
      (node (ref "C41") (pin "P$2") (pinfunction "2_P$2") (pintype "passive"))
      (node (ref "C42") (pin "P$2") (pinfunction "2_P$2") (pintype "passive"))
      (node (ref "C43") (pin "2") (pinfunction "2_2") (pintype "passive"))
      (node (ref "C44") (pin "P$2") (pinfunction "2_P$2") (pintype "passive"))
      (node (ref "C45") (pin "P$2") (pinfunction "2_P$2") (pintype "passive"))
      (node (ref "C46") (pin "P$2") (pinfunction "2_P$2") (pintype "passive"))
      (node (ref "C47") (pin "P$2") (pinfunction "2_P$2") (pintype "passive"))
      (node (ref "C48") (pin "2") (pinfunction "2_2") (pintype "passive"))
      (node (ref "C49") (pin "P$2") (pinfunction "2_P$2") (pintype "passive"))
      (node (ref "C5") (pin "P$2") (pinfunction "2_P$2") (pintype "passive"))
      (node (ref "C50") (pin "P$2") (pinfunction "2_P$2") (pintype "passive"))
      (node (ref "C51") (pin "P$2") (pinfunction "2_P$2") (pintype "passive"))
      (node (ref "C52") (pin "P$2") (pinfunction "2_P$2") (pintype "passive"))
      (node (ref "C53") (pin "P$2") (pinfunction "2_P$2") (pintype "passive"))
      (node (ref "C54") (pin "P$1") (pinfunction "1_P$1") (pintype "passive"))
      (node (ref "C55") (pin "P$1") (pinfunction "1_P$1") (pintype "passive"))
      (node (ref "C56") (pin "P$1") (pinfunction "1_P$1") (pintype "passive"))
      (node (ref "C57") (pin "P$2") (pinfunction "2_P$2") (pintype "passive"))
      (node (ref "C58") (pin "P$2") (pinfunction "2_P$2") (pintype "passive"))
      (node (ref "C59") (pin "P$2") (pinfunction "2_P$2") (pintype "passive"))
      (node (ref "C60") (pin "P$2") (pinfunction "2_P$2") (pintype "passive"))
      (node (ref "C61") (pin "P$1") (pinfunction "1_P$1") (pintype "passive"))
      (node (ref "C62") (pin "P$2") (pinfunction "2_P$2") (pintype "passive"))
      (node (ref "C63") (pin "P$2") (pinfunction "2_P$2") (pintype "passive"))
      (node (ref "C8") (pin "P$2") (pinfunction "2_P$2") (pintype "passive"))
      (node (ref "IC3") (pin "2") (pinfunction "GND_2") (pintype "power_in"))
      (node (ref "IC4") (pin "2") (pinfunction "GND_2") (pintype "power_in"))
      (node (ref "J1") (pin "P$19") (pinfunction "P$19_P$19") (pintype "bidirectional"))
      (node (ref "J11") (pin "10") (pinfunction "10_10") (pintype "passive"))
      (node (ref "J11") (pin "6") (pinfunction "6_6") (pintype "passive"))
      (node (ref "J11") (pin "8") (pinfunction "8_8") (pintype "passive"))
      (node (ref "J12") (pin "P$14") (pinfunction "GND_P$14") (pintype "power_in"))
      (node (ref "J12") (pin "P$20") (pinfunction "GND_P$20") (pintype "power_in"))
      (node (ref "J12") (pin "P$25") (pinfunction "GND_P$25") (pintype "power_in"))
      (node (ref "J12") (pin "P$30") (pinfunction "GND_P$30") (pintype "power_in"))
      (node (ref "J12") (pin "P$34") (pinfunction "GND_P$34") (pintype "power_in"))
      (node (ref "J12") (pin "P$39") (pinfunction "GND_P$39") (pintype "power_in"))
      (node (ref "J12") (pin "P$6") (pinfunction "GND_P$6") (pintype "power_in"))
      (node (ref "J12") (pin "P$9") (pinfunction "GND_P$9") (pintype "power_in"))
      (node (ref "J2") (pin "P$5") (pinfunction "GND_P$5") (pintype "bidirectional"))
      (node (ref "J3") (pin "GND") (pinfunction "GND_GND") (pintype "power_in"))
      (node (ref "J4") (pin "10") (pinfunction "GLO_10") (pintype "bidirectional"))
      (node (ref "J4") (pin "8") (pinfunction "P8_8") (pintype "bidirectional"))
      (node (ref "LED3") (pin "C") (pinfunction "C_C") (pintype "passive"))
      (node (ref "LED4") (pin "C") (pinfunction "C_C") (pintype "passive"))
      (node (ref "R14") (pin "P$1") (pinfunction "1_P$1") (pintype "passive"))
      (node (ref "R16") (pin "P$1") (pinfunction "1_P$1") (pintype "passive"))
      (node (ref "R17") (pin "P$1") (pinfunction "1_P$1") (pintype "passive"))
      (node (ref "R19") (pin "P$1") (pinfunction "1_P$1") (pintype "passive"))
      (node (ref "R21") (pin "P$1") (pinfunction "1_P$1") (pintype "passive"))
      (node (ref "R25") (pin "P$1") (pinfunction "1_P$1") (pintype "passive"))
      (node (ref "R7") (pin "P$1") (pinfunction "1_P$1") (pintype "passive"))
      (node (ref "U$2") (pin "P1") (pinfunction "GND_P1") (pintype "bidirectional"))
      (node (ref "U$2") (pin "P23") (pinfunction "GND2_P23") (pintype "bidirectional"))
      (node (ref "U$3") (pin "2") (pinfunction "2_2") (pintype "bidirectional"))
      (node (ref "U$3") (pin "4") (pinfunction "4_4") (pintype "bidirectional"))
      (node (ref "U$4") (pin "P$2") (pinfunction "2_P$2") (pintype "passive"))
      (node (ref "U$8") (pin "N-") (pinfunction "-_N-") (pintype "passive"))
      (node (ref "U2") (pin "2") (pinfunction "GND_2") (pintype "input"))
      (node (ref "U3") (pin "22") (pinfunction "GND_22") (pintype "power_in"))
      (node (ref "U3") (pin "25") (pinfunction "25_25") (pintype "passive"))
      (node (ref "U4") (pin "111") (pinfunction "VSS(IO)5_111") (pintype "bidirectional"))
      (node (ref "U4") (pin "124") (pinfunction "VSS(IO)6_124") (pintype "bidirectional"))
      (node (ref "U4") (pin "139") (pinfunction "VSS(IO)7_139") (pintype "bidirectional"))
      (node (ref "U4") (pin "150") (pinfunction "VSS(IO)8_150") (pintype "bidirectional"))
      (node (ref "U4") (pin "153") (pinfunction "VREFL_153") (pintype "bidirectional"))
      (node (ref "U4") (pin "156") (pinfunction "AVSS0_156") (pintype "bidirectional"))
      (node (ref "U4") (pin "157") (pinfunction "VREFL0_157") (pintype "bidirectional"))
      (node (ref "U4") (pin "170") (pinfunction "VSS(IO)9_170") (pintype "bidirectional"))
      (node (ref "U4") (pin "22") (pinfunction "VSS1_22") (pintype "bidirectional"))
      (node (ref "U4") (pin "28") (pinfunction "AVSS_USBHS_28") (pintype "bidirectional"))
      (node (ref "U4") (pin "29") (pinfunction "PVSS_USBHS_29") (pintype "bidirectional"))
      (node (ref "U4") (pin "30") (pinfunction "VSS2_USBHS_30") (pintype "bidirectional"))
      (node (ref "U4") (pin "33") (pinfunction "VSS1_USBHS_33") (pintype "bidirectional"))
      (node (ref "U4") (pin "35") (pinfunction "VSSIO_35") (pintype "bidirectional"))
      (node (ref "U4") (pin "45") (pinfunction "VSS_USB_45") (pintype "bidirectional"))
      (node (ref "U4") (pin "60") (pinfunction "VSS(IO)2_60") (pintype "bidirectional"))
      (node (ref "U4") (pin "63") (pinfunction "VSS(IO/DCDC)_63") (pintype "bidirectional"))
      (node (ref "U4") (pin "66") (pinfunction "VCC_DCDC(IO/DCDC)_66") (pintype "bidirectional"))
      (node (ref "U4") (pin "83") (pinfunction "VSS(IO)3_83") (pintype "bidirectional"))
      (node (ref "U4") (pin "98") (pinfunction "VSS(IO)4_98") (pintype "bidirectional"))
      (node (ref "U5") (pin "P$3") (pinfunction "VOUT-_P$3") (pintype "bidirectional"))
      (node (ref "U6") (pin "2") (pinfunction "REF_2") (pintype "passive"))
      (node (ref "U6") (pin "3") (pinfunction "VS-_3") (pintype "power_in"))
      (node (ref "U7") (pin "2") (pinfunction "REF_2") (pintype "passive"))
      (node (ref "U7") (pin "3") (pinfunction "VS-_3") (pintype "power_in"))
      (node (ref "X4") (pin "2") (pinfunction "2_2") (pintype "bidirectional"))
      (node (ref "X4") (pin "4") (pinfunction "4_4") (pintype "bidirectional"))
    )
    (net (code "32") (name "GNDE") (class "Default")
      (node (ref "J2") (pin "P$6") (pinfunction "SHIELD1_P$6") (pintype "bidirectional"))
      (node (ref "J2") (pin "P$7") (pinfunction "SHIELD2_P$7") (pintype "bidirectional"))
      (node (ref "J2") (pin "P$8") (pinfunction "SHIELD3_P$8") (pintype "bidirectional"))
      (node (ref "J2") (pin "P$9") (pinfunction "SHIELD4_P$9") (pintype "bidirectional"))
      (node (ref "J3") (pin "SHLD1") (pinfunction "SHIELD_1_SHLD1") (pintype "bidirectional"))
      (node (ref "J3") (pin "SHLD2") (pinfunction "SHIELD_2_SHLD2") (pintype "bidirectional"))
      (node (ref "J4") (pin "13") (pinfunction "GNDE0_13") (pintype "bidirectional"))
      (node (ref "J4") (pin "14") (pinfunction "GNDE1_14") (pintype "bidirectional"))
    )
    (net (code "33") (name "GP4") (class "Default")
      (node (ref "J12") (pin "P$7") (pinfunction "GP4_P$7") (pintype "bidirectional"))
      (node (ref "U4") (pin "49") (pinfunction "P2_7_49") (pintype "bidirectional"))
    )
    (net (code "34") (name "GP5") (class "Default")
      (node (ref "J12") (pin "P$29") (pinfunction "GP5_P$29") (pintype "bidirectional"))
      (node (ref "U4") (pin "57") (pinfunction "P3_15_57") (pintype "bidirectional"))
    )
    (net (code "35") (name "GP6") (class "Default")
      (node (ref "J12") (pin "P$31") (pinfunction "GP6_P$31") (pintype "bidirectional"))
      (node (ref "U4") (pin "59") (pinfunction "P9_1_59") (pintype "bidirectional"))
    )
    (net (code "36") (name "GP12") (class "Default")
      (node (ref "J12") (pin "P$32") (pinfunction "GP12_P$32") (pintype "bidirectional"))
      (node (ref "U4") (pin "58") (pinfunction "P9_0_58") (pintype "bidirectional"))
    )
    (net (code "37") (name "GP13") (class "Default")
      (node (ref "J12") (pin "P$33") (pinfunction "GP13_P$33") (pintype "bidirectional"))
      (node (ref "U4") (pin "76") (pinfunction "P3_10_76") (pintype "bidirectional"))
    )
    (net (code "38") (name "GP14") (class "Default")
      (node (ref "J12") (pin "P$8") (pinfunction "TXO_P$8") (pintype "output"))
      (node (ref "U4") (pin "42") (pinfunction "P4_9_42") (pintype "bidirectional"))
    )
    (net (code "39") (name "GP15") (class "Default")
      (node (ref "J12") (pin "P$10") (pinfunction "RXI_P$10") (pintype "input"))
      (node (ref "U4") (pin "43") (pinfunction "P4_8_43") (pintype "bidirectional"))
    )
    (net (code "40") (name "GP16") (class "Default")
      (node (ref "J12") (pin "P$36") (pinfunction "GP16_P$36") (pintype "bidirectional"))
      (node (ref "U4") (pin "79") (pinfunction "P3_7_79") (pintype "bidirectional"))
    )
    (net (code "41") (name "GP17") (class "Default")
      (node (ref "J12") (pin "P$11") (pinfunction "GP17_P$11") (pintype "bidirectional"))
      (node (ref "U4") (pin "51") (pinfunction "P2_5_51") (pintype "bidirectional"))
    )
    (net (code "42") (name "GP18") (class "Default")
      (node (ref "J12") (pin "P$12") (pinfunction "GP18#_P$12") (pintype "bidirectional"))
      (node (ref "U4") (pin "50") (pinfunction "P2_6_50") (pintype "bidirectional"))
    )
    (net (code "43") (name "GP19") (class "Default")
      (node (ref "J12") (pin "P$35") (pinfunction "GP19_P$35") (pintype "bidirectional"))
      (node (ref "U4") (pin "77") (pinfunction "P3_9_77") (pintype "bidirectional"))
    )
    (net (code "44") (name "GP20") (class "Default")
      (node (ref "J12") (pin "P$38") (pinfunction "GP20_P$38") (pintype "bidirectional"))
      (node (ref "U4") (pin "81") (pinfunction "P3_5_81") (pintype "bidirectional"))
    )
    (net (code "45") (name "GP21") (class "Default")
      (node (ref "J12") (pin "P$40") (pinfunction "GP21_P$40") (pintype "bidirectional"))
      (node (ref "U4") (pin "82") (pinfunction "P3_4_82") (pintype "bidirectional"))
    )
    (net (code "46") (name "GP22") (class "Default")
      (node (ref "J12") (pin "P$15") (pinfunction "GP22_P$15") (pintype "bidirectional"))
      (node (ref "U4") (pin "72") (pinfunction "P9_6_72") (pintype "bidirectional"))
    )
    (net (code "47") (name "GP23") (class "Default")
      (node (ref "J12") (pin "P$16") (pinfunction "GP23_P$16") (pintype "bidirectional"))
      (node (ref "U4") (pin "71") (pinfunction "P9_7_71") (pintype "bidirectional"))
    )
    (net (code "48") (name "GP24") (class "Default")
      (node (ref "J12") (pin "P$18") (pinfunction "GP24_P$18") (pintype "bidirectional"))
      (node (ref "U4") (pin "73") (pinfunction "P9_5_73") (pintype "bidirectional"))
    )
    (net (code "49") (name "GP25") (class "Default")
      (node (ref "J12") (pin "P$22") (pinfunction "GP25_P$22") (pintype "bidirectional"))
      (node (ref "U4") (pin "56") (pinfunction "P3_14_56") (pintype "bidirectional"))
    )
    (net (code "50") (name "GP26") (class "Default")
      (node (ref "J12") (pin "P$37") (pinfunction "GP26_P$37") (pintype "bidirectional"))
      (node (ref "U4") (pin "80") (pinfunction "P3_6_80") (pintype "bidirectional"))
    )
    (net (code "51") (name "GP27") (class "Default")
      (node (ref "J12") (pin "P$13") (pinfunction "GP27_P$13") (pintype "bidirectional"))
      (node (ref "U4") (pin "70") (pinfunction "P9_8_70") (pintype "bidirectional"))
    )
    (net (code "52") (name "ID") (class "Default")
      (node (ref "J2") (pin "P$4") (pinfunction "ID_P$4") (pintype "bidirectional"))
    )
    (net (code "53") (name "ID_SC") (class "Default")
      (node (ref "J12") (pin "P$28") (pinfunction "ID_SC_P$28") (pintype "bidirectional"))
      (node (ref "U4") (pin "93") (pinfunction "P1_12_93") (pintype "bidirectional"))
    )
    (net (code "54") (name "ID_SD") (class "Default")
      (node (ref "J12") (pin "P$27") (pinfunction "ID_SD_P$27") (pintype "bidirectional"))
      (node (ref "U4") (pin "92") (pinfunction "P1_11_92") (pintype "bidirectional"))
    )
    (net (code "55") (name "IIC_0_SCL") (class "Default")
      (node (ref "J12") (pin "P$5") (pinfunction "SCL_P$5") (pintype "bidirectional"))
      (node (ref "U4") (pin "1") (pinfunction "P4_0_1") (pintype "bidirectional"))
    )
    (net (code "56") (name "IIC_0_SDA") (class "Default")
      (node (ref "J12") (pin "P$3") (pinfunction "SDA_P$3") (pintype "bidirectional"))
      (node (ref "U4") (pin "2") (pinfunction "P4_1_2") (pintype "bidirectional"))
    )
    (net (code "57") (name "IRQ0") (class "Default")
      (node (ref "U$2") (pin "P10") (pinfunction "IRQ0_P10") (pintype "bidirectional"))
      (node (ref "U4") (pin "86") (pinfunction "P3_2_86") (pintype "bidirectional"))
    )
    (net (code "58") (name "IRQ1") (class "Default")
      (node (ref "U$2") (pin "P11") (pinfunction "IRQ1_P11") (pintype "bidirectional"))
      (node (ref "U4") (pin "87") (pinfunction "P3_1_87") (pintype "bidirectional"))
    )
    (net (code "59") (name "LED1{slash}SPEED") (class "Default")
      (node (ref "J4") (pin "11") (pinfunction "YLO_11") (pintype "bidirectional"))
      (node (ref "U3") (pin "23") (pinfunction "LED0/ANEN_SPEED_23") (pintype "bidirectional"))
    )
    (net (code "60") (name "M0_STEP") (class "Default")
      (node (ref "U4") (pin "16") (pinfunction "PB_0_16") (pintype "bidirectional"))
    )
    (net (code "61") (name "N") (class "Default")
      (node (ref "C20") (pin "P$2") (pinfunction "P$2_P$2") (pintype "bidirectional"))
      (node (ref "U$2") (pin "P21") (pinfunction "GND1_P21") (pintype "bidirectional"))
      (node (ref "U$7") (pin "P$2") (pinfunction "P$2_P$2") (pintype "bidirectional"))
      (node (ref "U5") (pin "P$6") (pinfunction "AC_N_P$6") (pintype "bidirectional"))
    )
    (net (code "62") (name "NC") (class "Default")
      (node (ref "J4") (pin "7") (pinfunction "P7_7") (pintype "bidirectional"))
    )
    (net (code "63") (name "Net-(C16-1)") (class "Default")
      (node (ref "C16") (pin "P$1") (pinfunction "1_P$1") (pintype "passive"))
      (node (ref "J2") (pin "P$1") (pinfunction "VBUS_P$1") (pintype "bidirectional"))
      (node (ref "R4") (pin "P$2") (pinfunction "2_P$2") (pintype "passive"))
      (node (ref "R7") (pin "P$2") (pinfunction "2_P$2") (pintype "passive"))
    )
    (net (code "64") (name "Net-(C31-1)") (class "Default")
      (node (ref "C31") (pin "P$1") (pinfunction "1_P$1") (pintype "passive"))
      (node (ref "U4") (pin "62") (pinfunction "VCL1_62") (pintype "bidirectional"))
    )
    (net (code "65") (name "Net-(C37-2)") (class "Default")
      (node (ref "C37") (pin "P$2") (pinfunction "2_P$2") (pintype "passive"))
      (node (ref "U4") (pin "148") (pinfunction "VCL2_148") (pintype "bidirectional"))
    )
    (net (code "66") (name "Net-(C38-1)") (class "Default")
      (node (ref "C38") (pin "P$1") (pinfunction "1_P$1") (pintype "passive"))
      (node (ref "U4") (pin "19") (pinfunction "VCLO_19") (pintype "bidirectional"))
    )
    (net (code "67") (name "Net-(C44-1)") (class "Default")
      (node (ref "C43") (pin "1") (pinfunction "1_1") (pintype "passive"))
      (node (ref "C44") (pin "P$1") (pinfunction "1_P$1") (pintype "passive"))
      (node (ref "FB2/2") (pin "2") (pinfunction "P$2_2") (pintype "bidirectional"))
      (node (ref "U3") (pin "2") (pinfunction "VDDA_3.3_2") (pintype "power_in"))
    )
    (net (code "68") (name "Net-(J2-D+)") (class "Default")
      (node (ref "J2") (pin "P$3") (pinfunction "D+_P$3") (pintype "bidirectional"))
      (node (ref "R6") (pin "P$2") (pinfunction "2_P$2") (pintype "passive"))
    )
    (net (code "69") (name "Net-(J2-D-)") (class "Default")
      (node (ref "J2") (pin "P$2") (pinfunction "D-_P$2") (pintype "bidirectional"))
      (node (ref "R5") (pin "P$2") (pinfunction "2_P$2") (pintype "passive"))
    )
    (net (code "70") (name "Net-(R8-2)") (class "Default")
      (node (ref "LED3") (pin "A") (pinfunction "A_A") (pintype "passive"))
      (node (ref "R8") (pin "P$2") (pinfunction "2_P$2") (pintype "passive"))
    )
    (net (code "71") (name "Net-(R9-2)") (class "Default")
      (node (ref "LED4") (pin "A") (pinfunction "A_A") (pintype "passive"))
      (node (ref "R9") (pin "P$2") (pinfunction "2_P$2") (pintype "passive"))
    )
    (net (code "72") (name "Net-(R16-2)") (class "Default")
      (node (ref "R16") (pin "P$2") (pinfunction "2_P$2") (pintype "passive"))
      (node (ref "U4") (pin "65") (pinfunction "VLO2(DCDC)_65") (pintype "bidirectional"))
    )
    (net (code "73") (name "Net-(R17-2)") (class "Default")
      (node (ref "R17") (pin "P$2") (pinfunction "2_P$2") (pintype "passive"))
      (node (ref "U4") (pin "64") (pinfunction "VLO1(DCDC)_64") (pintype "bidirectional"))
    )
    (net (code "74") (name "Net-(R19-2)") (class "Default")
      (node (ref "R19") (pin "P$2") (pinfunction "2_P$2") (pintype "passive"))
      (node (ref "U4") (pin "27") (pinfunction "USBHS_RREF_27") (pintype "bidirectional"))
    )
    (net (code "75") (name "P0_02") (class "Default")
      (node (ref "J1") (pin "P$6") (pinfunction "P$6_P$6") (pintype "bidirectional"))
      (node (ref "U4") (pin "167") (pinfunction "P0_2/AN002_167") (pintype "bidirectional"))
    )
    (net (code "76") (name "P0_03") (class "Default")
      (node (ref "J1") (pin "P$5") (pinfunction "P$5_P$5") (pintype "bidirectional"))
      (node (ref "U4") (pin "166") (pinfunction "P0_3/PGAVSS000_166") (pintype "bidirectional"))
    )
    (net (code "77") (name "P0_04") (class "Default")
      (node (ref "J1") (pin "P$8") (pinfunction "P$8_P$8") (pintype "bidirectional"))
      (node (ref "U4") (pin "165") (pinfunction "P0_4/AN100_165") (pintype "bidirectional"))
    )
    (net (code "78") (name "P0_07") (class "Default")
      (node (ref "J1") (pin "P$7") (pinfunction "P$7_P$7") (pintype "bidirectional"))
      (node (ref "U4") (pin "162") (pinfunction "P0_7/PGVSS100_162") (pintype "bidirectional"))
    )
    (net (code "79") (name "P0_14") (class "Default")
      (node (ref "J1") (pin "P$10") (pinfunction "P$10_P$10") (pintype "bidirectional"))
      (node (ref "U4") (pin "152") (pinfunction "P0_14/DA0/AN005/AN105_152") (pintype "bidirectional"))
    )
    (net (code "80") (name "P0_15") (class "Default")
      (node (ref "J1") (pin "P$9") (pinfunction "P$9_P$9") (pintype "bidirectional"))
      (node (ref "U4") (pin "151") (pinfunction "P0_15/DA1/AN006/AN106_151") (pintype "bidirectional"))
    )
    (net (code "81") (name "P1_05") (class "Default")
      (node (ref "U4") (pin "127") (pinfunction "P1_5_127") (pintype "bidirectional"))
    )
    (net (code "82") (name "P1_13") (class "Default")
      (node (ref "U4") (pin "94") (pinfunction "P1_13_94") (pintype "bidirectional"))
    )
    (net (code "83") (name "P1_14") (class "Default")
      (node (ref "U4") (pin "95") (pinfunction "P1_14_95") (pintype "bidirectional"))
    )
    (net (code "84") (name "P1_15") (class "Default")
      (node (ref "U4") (pin "96") (pinfunction "P1_15_96") (pintype "bidirectional"))
    )
    (net (code "85") (name "P2_00") (class "Default")
      (node (ref "U4") (pin "69") (pinfunction "P2_0(INPUT_ONLY)_69") (pintype "bidirectional"))
    )
    (net (code "86") (name "P2_01") (class "Default")
      (node (ref "U4") (pin "68") (pinfunction "P2_1/MD_68") (pintype "bidirectional"))
    )
    (net (code "87") (name "P3_03") (class "Default")
      (node (ref "U4") (pin "85") (pinfunction "P3_3_85") (pintype "bidirectional"))
    )
    (net (code "88") (name "P3_11") (class "Default")
      (node (ref "U4") (pin "75") (pinfunction "P3_11_75") (pintype "bidirectional"))
    )
    (net (code "89") (name "P4_02") (class "Default")
      (node (ref "U4") (pin "3") (pinfunction "P4_2_3") (pintype "bidirectional"))
    )
    (net (code "90") (name "P4_10") (class "Default")
      (node (ref "U4") (pin "41") (pinfunction "P4_10_41") (pintype "bidirectional"))
    )
    (net (code "91") (name "P4_11") (class "Default")
      (node (ref "U4") (pin "40") (pinfunction "P4_11_40") (pintype "bidirectional"))
    )
    (net (code "92") (name "P4_12") (class "Default")
      (node (ref "U4") (pin "39") (pinfunction "P4_12_39") (pintype "bidirectional"))
    )
    (net (code "93") (name "P4_13") (class "Default")
      (node (ref "U4") (pin "38") (pinfunction "P4_13_38") (pintype "bidirectional"))
    )
    (net (code "94") (name "P4_14") (class "Default")
      (node (ref "U4") (pin "37") (pinfunction "P4_14_37") (pintype "bidirectional"))
    )
    (net (code "95") (name "P4_15") (class "Default")
      (node (ref "U4") (pin "36") (pinfunction "P4_15_36") (pintype "bidirectional"))
    )
    (net (code "96") (name "P5_00") (class "Default")
      (node (ref "J1") (pin "P$17") (pinfunction "P$17_P$17") (pintype "bidirectional"))
      (node (ref "U4") (pin "140") (pinfunction "P5_0/AN016_140") (pintype "bidirectional"))
    )
    (net (code "97") (name "P5_01") (class "Default")
      (node (ref "J1") (pin "P$18") (pinfunction "P$18_P$18") (pintype "bidirectional"))
      (node (ref "U4") (pin "141") (pinfunction "P5_1/AN116_141") (pintype "bidirectional"))
    )
    (net (code "98") (name "P5_02") (class "Default")
      (node (ref "J1") (pin "P$15") (pinfunction "P$15_P$15") (pintype "bidirectional"))
      (node (ref "U4") (pin "142") (pinfunction "P5_2/AN017_142") (pintype "bidirectional"))
    )
    (net (code "99") (name "P5_03") (class "Default")
      (node (ref "J1") (pin "P$16") (pinfunction "P$16_P$16") (pintype "bidirectional"))
      (node (ref "U4") (pin "143") (pinfunction "P5_3/AN117_143") (pintype "bidirectional"))
    )
    (net (code "100") (name "P5_04") (class "Default")
      (node (ref "J1") (pin "P$13") (pinfunction "P$13_P$13") (pintype "bidirectional"))
      (node (ref "U4") (pin "144") (pinfunction "P5_4/AN018_144") (pintype "bidirectional"))
    )
    (net (code "101") (name "P5_05") (class "Default")
      (node (ref "J1") (pin "P$14") (pinfunction "P$14_P$14") (pintype "bidirectional"))
      (node (ref "U4") (pin "145") (pinfunction "P5_5/AN118_145") (pintype "bidirectional"))
    )
    (net (code "102") (name "P5_06") (class "Default")
      (node (ref "J1") (pin "P$11") (pinfunction "P$11_P$11") (pintype "bidirectional"))
      (node (ref "U4") (pin "146") (pinfunction "P5_6/AN019_146") (pintype "bidirectional"))
    )
    (net (code "103") (name "P5_07") (class "Default")
      (node (ref "J1") (pin "P$12") (pinfunction "P$12_P$12") (pintype "bidirectional"))
      (node (ref "U4") (pin "147") (pinfunction "P5_7/AN119_147") (pintype "bidirectional"))
    )
    (net (code "104") (name "P5_11") (class "Default")
      (node (ref "J1") (pin "P$2") (pinfunction "P$2_P$2") (pintype "bidirectional"))
      (node (ref "U4") (pin "176") (pinfunction "P5_11_176") (pintype "bidirectional"))
    )
    (net (code "105") (name "P5_12") (class "Default")
      (node (ref "J1") (pin "P$1") (pinfunction "P$1_P$1") (pintype "bidirectional"))
      (node (ref "U4") (pin "175") (pinfunction "P5_12_175") (pintype "bidirectional"))
    )
    (net (code "106") (name "P5_13") (class "Default")
      (node (ref "J1") (pin "P$4") (pinfunction "P$4_P$4") (pintype "bidirectional"))
      (node (ref "U4") (pin "174") (pinfunction "P5_13_174") (pintype "bidirectional"))
    )
    (net (code "107") (name "P6_02") (class "Default")
      (node (ref "U4") (pin "120") (pinfunction "P6_2_120") (pintype "bidirectional"))
    )
    (net (code "108") (name "P6_03") (class "Default")
      (node (ref "U4") (pin "119") (pinfunction "P6_3_119") (pintype "bidirectional"))
    )
    (net (code "109") (name "P6_04") (class "Default")
      (node (ref "U4") (pin "118") (pinfunction "P6_4_118") (pintype "bidirectional"))
    )
    (net (code "110") (name "P6_05") (class "Default")
      (node (ref "U4") (pin "117") (pinfunction "P6_5_117") (pintype "bidirectional"))
    )
    (net (code "111") (name "P6_06") (class "Default")
      (node (ref "U4") (pin "116") (pinfunction "P6_6_116") (pintype "bidirectional"))
    )
    (net (code "112") (name "P6_07") (class "Default")
      (node (ref "U4") (pin "115") (pinfunction "P6_7_115") (pintype "bidirectional"))
    )
    (net (code "113") (name "P6_08") (class "Default")
      (node (ref "U4") (pin "99") (pinfunction "P6_8_99") (pintype "bidirectional"))
    )
    (net (code "114") (name "P6_09") (class "Default")
      (node (ref "U4") (pin "100") (pinfunction "P6_9_100") (pintype "bidirectional"))
    )
    (net (code "115") (name "P6_10") (class "Default")
      (node (ref "U4") (pin "101") (pinfunction "P6_10_101") (pintype "bidirectional"))
    )
    (net (code "116") (name "P6_11") (class "Default")
      (node (ref "U4") (pin "102") (pinfunction "P6_11_102") (pintype "bidirectional"))
    )
    (net (code "117") (name "P6_12") (class "Default")
      (node (ref "U4") (pin "103") (pinfunction "P6_12_103") (pintype "bidirectional"))
    )
    (net (code "118") (name "P6_13") (class "Default")
      (node (ref "U4") (pin "104") (pinfunction "P6_13_104") (pintype "bidirectional"))
    )
    (net (code "119") (name "P6_14") (class "Default")
      (node (ref "U4") (pin "105") (pinfunction "P6_14_105") (pintype "bidirectional"))
    )
    (net (code "120") (name "P6_15") (class "Default")
      (node (ref "U4") (pin "106") (pinfunction "P6_15_106") (pintype "bidirectional"))
    )
    (net (code "121") (name "P7_06") (class "Default")
      (node (ref "U4") (pin "14") (pinfunction "P7_6_14") (pintype "bidirectional"))
    )
    (net (code "122") (name "P7_07") (class "Default")
      (node (ref "U4") (pin "15") (pinfunction "P7_7_15") (pintype "bidirectional"))
    )
    (net (code "123") (name "P8_03") (class "Default")
      (node (ref "U4") (pin "136") (pinfunction "P8_3_136") (pintype "bidirectional"))
    )
    (net (code "124") (name "P8_04") (class "Default")
      (node (ref "U4") (pin "137") (pinfunction "P8_4_137") (pintype "bidirectional"))
    )
    (net (code "125") (name "P8_05") (class "Default")
      (node (ref "J1") (pin "P$3") (pinfunction "P$3_P$3") (pintype "bidirectional"))
      (node (ref "U4") (pin "173") (pinfunction "P8_5_173") (pintype "bidirectional"))
    )
    (net (code "126") (name "PA_00") (class "Default")
      (node (ref "U4") (pin "114") (pinfunction "PA_0_114") (pintype "bidirectional"))
    )
    (net (code "127") (name "PA_01") (class "Default")
      (node (ref "U4") (pin "113") (pinfunction "PA_1_113") (pintype "bidirectional"))
    )
    (net (code "128") (name "PA_08") (class "Default")
      (node (ref "U4") (pin "107") (pinfunction "PA_8_107") (pintype "bidirectional"))
    )
    (net (code "129") (name "PA_09") (class "Default")
      (node (ref "U4") (pin "108") (pinfunction "PA_9_108") (pintype "bidirectional"))
    )
    (net (code "130") (name "PA_10") (class "Default")
      (node (ref "U4") (pin "109") (pinfunction "PA_10_109") (pintype "bidirectional"))
    )
    (net (code "131") (name "PM0") (class "Default")
      (node (ref "U$2") (pin "P12") (pinfunction "PM0_P12") (pintype "bidirectional"))
      (node (ref "U4") (pin "126") (pinfunction "P1_6_126") (pintype "bidirectional"))
    )
    (net (code "132") (name "PM1") (class "Default")
      (node (ref "U$2") (pin "P13") (pinfunction "PM1_P13") (pintype "bidirectional"))
      (node (ref "U4") (pin "125") (pinfunction "P1_7_125") (pintype "bidirectional"))
    )
    (net (code "133") (name "R51") (class "Default")
      (node (ref "J4") (pin "12") (pinfunction "YHI_12") (pintype "bidirectional"))
      (node (ref "R23") (pin "P$1") (pinfunction "1_P$1") (pintype "passive"))
    )
    (net (code "134") (name "R52") (class "Default")
      (node (ref "J4") (pin "9") (pinfunction "GHI_9") (pintype "bidirectional"))
      (node (ref "R24") (pin "P$1") (pinfunction "1_P$1") (pintype "passive"))
    )
    (net (code "135") (name "RESET") (class "Default")
      (node (ref "C57") (pin "P$1") (pinfunction "1_P$1") (pintype "passive"))
      (node (ref "J11") (pin "9") (pinfunction "9_9") (pintype "passive"))
      (node (ref "R18") (pin "P$1") (pinfunction "1_P$1") (pintype "passive"))
      (node (ref "U4") (pin "67") (pinfunction "RES#_67") (pintype "bidirectional"))
    )
    (net (code "136") (name "REXT") (class "Default")
      (node (ref "C47") (pin "P$1") (pinfunction "1_P$1") (pintype "passive"))
      (node (ref "R25") (pin "P$2") (pinfunction "2_P$2") (pintype "passive"))
      (node (ref "U3") (pin "9") (pinfunction "REXT_9") (pintype "input"))
    )
    (net (code "137") (name "RST") (class "Default")
      (node (ref "U$2") (pin "P20") (pinfunction "RST_P20") (pintype "bidirectional"))
      (node (ref "U4") (pin "121") (pinfunction "P6_1_121") (pintype "bidirectional"))
    )
    (net (code "138") (name "RXD0") (class "Default")
      (node (ref "R31") (pin "P$2") (pinfunction "2_P$2") (pintype "passive"))
      (node (ref "U3") (pin "13") (pinfunction "RXD0_13") (pintype "bidirectional"))
    )
    (net (code "139") (name "RXD1") (class "Default")
      (node (ref "R30") (pin "P$2") (pinfunction "2_P$2") (pintype "passive"))
      (node (ref "U3") (pin "12") (pinfunction "RXD1_12") (pintype "bidirectional"))
    )
    (net (code "140") (name "RXER") (class "Default")
      (node (ref "R32") (pin "P$2") (pinfunction "2_P$2") (pintype "passive"))
      (node (ref "U3") (pin "17") (pinfunction "RXER_17") (pintype "bidirectional"))
    )
    (net (code "141") (name "RXM") (class "Default")
      (node (ref "J4") (pin "6") (pinfunction "RD-_6") (pintype "bidirectional"))
      (node (ref "U3") (pin "3") (pinfunction "RXM_3") (pintype "bidirectional"))
    )
    (net (code "142") (name "RXP") (class "Default")
      (node (ref "J4") (pin "3") (pinfunction "RD+_3") (pintype "bidirectional"))
      (node (ref "U3") (pin "4") (pinfunction "RXP_4") (pintype "bidirectional"))
    )
    (net (code "143") (name "SPI_0_CS_0") (class "Default")
      (node (ref "U$2") (pin "P16") (pinfunction "CS_P16") (pintype "bidirectional"))
      (node (ref "U4") (pin "129") (pinfunction "P1_3_129") (pintype "bidirectional"))
    )
    (net (code "144") (name "SPI_0_MISO") (class "Default")
      (node (ref "U$2") (pin "P18") (pinfunction "SDO_P18") (pintype "bidirectional"))
      (node (ref "U4") (pin "132") (pinfunction "P1_0_132") (pintype "bidirectional"))
    )
    (net (code "145") (name "SPI_0_MOSI") (class "Default")
      (node (ref "U$2") (pin "P15") (pinfunction "SDI_P15") (pintype "bidirectional"))
      (node (ref "U4") (pin "131") (pinfunction "P1_1_131") (pintype "bidirectional"))
    )
    (net (code "146") (name "SPI_0_SCLK") (class "Default")
      (node (ref "U$2") (pin "P17") (pinfunction "SCLK_P17") (pintype "bidirectional"))
      (node (ref "U4") (pin "130") (pinfunction "P1_2_130") (pintype "bidirectional"))
    )
    (net (code "147") (name "SPI_1_CS_0") (class "Default")
      (node (ref "J12") (pin "P$24") (pinfunction "CE0_P$24") (pintype "output"))
      (node (ref "U4") (pin "55") (pinfunction "P3_13_55") (pintype "bidirectional"))
    )
    (net (code "148") (name "SPI_1_CS_1") (class "Default")
      (node (ref "J12") (pin "P$26") (pinfunction "CE1_P$26") (pintype "output"))
      (node (ref "U4") (pin "74") (pinfunction "P3_12_74") (pintype "bidirectional"))
    )
    (net (code "149") (name "SPI_1_MISO") (class "Default")
      (node (ref "J12") (pin "P$21") (pinfunction "MISO_P$21") (pintype "input"))
      (node (ref "U4") (pin "54") (pinfunction "P2_2_54") (pintype "bidirectional"))
    )
    (net (code "150") (name "SPI_1_MOSI") (class "Default")
      (node (ref "J12") (pin "P$19") (pinfunction "MOSI_P$19") (pintype "output"))
      (node (ref "U4") (pin "53") (pinfunction "P2_3_53") (pintype "bidirectional"))
    )
    (net (code "151") (name "SPI_1_SCLK") (class "Default")
      (node (ref "J12") (pin "P$23") (pinfunction "SCLK_P$23") (pintype "output"))
      (node (ref "U4") (pin "52") (pinfunction "P2_4_52") (pintype "bidirectional"))
    )
    (net (code "152") (name "TCK") (class "Default")
      (node (ref "J11") (pin "7") (pinfunction "7_7") (pintype "passive"))
      (node (ref "U4") (pin "88") (pinfunction "P3_0_88") (pintype "bidirectional"))
    )
    (net (code "153") (name "TDI") (class "Default")
      (node (ref "J11") (pin "1") (pinfunction "1_1") (pintype "passive"))
      (node (ref "U4") (pin "91") (pinfunction "P1_10_91") (pintype "bidirectional"))
    )
    (net (code "154") (name "TDO") (class "Default")
      (node (ref "J11") (pin "3") (pinfunction "3_3") (pintype "passive"))
      (node (ref "U4") (pin "90") (pinfunction "P1_9_90") (pintype "bidirectional"))
    )
    (net (code "155") (name "TMS") (class "Default")
      (node (ref "J11") (pin "5") (pinfunction "5_5") (pintype "passive"))
      (node (ref "U4") (pin "89") (pinfunction "P1_8_89") (pintype "bidirectional"))
    )
    (net (code "156") (name "TXM") (class "Default")
      (node (ref "J4") (pin "2") (pinfunction "TD-_2") (pintype "bidirectional"))
      (node (ref "U3") (pin "5") (pinfunction "TXM_5") (pintype "bidirectional"))
    )
    (net (code "157") (name "TXP") (class "Default")
      (node (ref "J4") (pin "1") (pinfunction "TD+_1") (pintype "bidirectional"))
      (node (ref "U3") (pin "6") (pinfunction "TXP_6") (pintype "bidirectional"))
    )
    (net (code "158") (name "UC") (class "Default")
      (node (ref "C20") (pin "P$1") (pinfunction "P$1_P$1") (pintype "bidirectional"))
      (node (ref "U$2") (pin "P22") (pinfunction "VAC_240_P22") (pintype "bidirectional"))
      (node (ref "U$7") (pin "P$1") (pinfunction "P$1_P$1") (pintype "bidirectional"))
      (node (ref "U5") (pin "P$5") (pinfunction "AC_L_P$5") (pintype "bidirectional"))
    )
    (net (code "159") (name "USBHS_FAULT") (class "Default")
      (node (ref "R12") (pin "P$1") (pinfunction "1_P$1") (pintype "passive"))
      (node (ref "U2") (pin "3") (pinfunction "FLG_3") (pintype "input"))
      (node (ref "U4") (pin "78") (pinfunction "P3_8_78") (pintype "bidirectional"))
    )
    (net (code "160") (name "USBHS_N") (class "Default")
      (node (ref "J3") (pin "D-") (pinfunction "D-_D-") (pintype "bidirectional"))
      (node (ref "U4") (pin "31") (pinfunction "USBHS_DM_31") (pintype "bidirectional"))
    )
    (net (code "161") (name "USBHS_P") (class "Default")
      (node (ref "J3") (pin "D+") (pinfunction "D+_D+") (pintype "bidirectional"))
      (node (ref "U4") (pin "32") (pinfunction "USBHS_DP_32") (pintype "bidirectional"))
    )
    (net (code "162") (name "USBHS_VBUS") (class "Default")
      (node (ref "C11") (pin "P$1") (pinfunction "1_P$1") (pintype "passive"))
      (node (ref "C15") (pin "1") (pinfunction "1_1") (pintype "passive"))
      (node (ref "J3") (pin "VBUS") (pinfunction "VBUS_VBUS") (pintype "power_in"))
      (node (ref "U2") (pin "5") (pinfunction "OUT_5") (pintype "input"))
      (node (ref "U4") (pin "17") (pinfunction "PB_1_17") (pintype "bidirectional"))
    )
    (net (code "163") (name "USBHS_VBUSEN") (class "Default")
      (node (ref "R1") (pin "P$1") (pinfunction "1_P$1") (pintype "passive"))
      (node (ref "U2") (pin "1") (pinfunction "EN_1") (pintype "input"))
    )
    (net (code "164") (name "USB_N") (class "Default")
      (node (ref "R5") (pin "P$1") (pinfunction "1_P$1") (pintype "passive"))
      (node (ref "U4") (pin "46") (pinfunction "USB_DM_46") (pintype "bidirectional"))
    )
    (net (code "165") (name "USB_P") (class "Default")
      (node (ref "R6") (pin "P$1") (pinfunction "1_P$1") (pintype "passive"))
      (node (ref "U4") (pin "47") (pinfunction "USB_DP_47") (pintype "bidirectional"))
    )
    (net (code "166") (name "USB_VBUS_B") (class "Default")
      (node (ref "R4") (pin "P$1") (pinfunction "1_P$1") (pintype "passive"))
      (node (ref "U4") (pin "44") (pinfunction "P4_7_44") (pintype "bidirectional"))
    )
    (net (code "167") (name "VCC") (class "Default")
      (node (ref "C21") (pin "P$1") (pinfunction "1_P$1") (pintype "passive"))
      (node (ref "C22") (pin "P$1") (pinfunction "1_P$1") (pintype "passive"))
      (node (ref "C23") (pin "1") (pinfunction "1_1") (pintype "passive"))
      (node (ref "C24") (pin "P$1") (pinfunction "1_P$1") (pintype "passive"))
      (node (ref "IC3") (pin "1") (pinfunction "IN_1") (pintype "input"))
      (node (ref "IC4") (pin "1") (pinfunction "IN_1") (pintype "input"))
      (node (ref "U$8") (pin "P+") (pinfunction "+_P+") (pintype "passive"))
      (node (ref "U5") (pin "P$2") (pinfunction "VOUT+_P$2") (pintype "bidirectional"))
    )
    (net (code "168") (name "VCL_F(FLASH)") (class "Default")
      (node (ref "C36") (pin "P$2") (pinfunction "2_P$2") (pintype "passive"))
      (node (ref "U4") (pin "112") (pinfunction "VCL_F(FLASH)_112") (pintype "bidirectional"))
    )
    (net (code "169") (name "VDD") (class "Default")
      (node (ref "C1") (pin "P$2") (pinfunction "2_P$2") (pintype "passive"))
      (node (ref "C10") (pin "P$2") (pinfunction "2_P$2") (pintype "passive"))
      (node (ref "C13") (pin "P$2") (pinfunction "2_P$2") (pintype "passive"))
      (node (ref "C14") (pin "P$2") (pinfunction "2_P$2") (pintype "passive"))
      (node (ref "C19") (pin "P$1") (pinfunction "1_P$1") (pintype "passive"))
      (node (ref "C2") (pin "P$2") (pinfunction "2_P$2") (pintype "passive"))
      (node (ref "C25") (pin "P$1") (pinfunction "1_P$1") (pintype "passive"))
      (node (ref "C26") (pin "1") (pinfunction "1_1") (pintype "passive"))
      (node (ref "C29") (pin "P$1") (pinfunction "1_P$1") (pintype "passive"))
      (node (ref "C30") (pin "P$2") (pinfunction "2_P$2") (pintype "passive"))
      (node (ref "C32") (pin "P$1") (pinfunction "1_P$1") (pintype "passive"))
      (node (ref "C48") (pin "1") (pinfunction "1_1") (pintype "passive"))
      (node (ref "C49") (pin "P$1") (pinfunction "1_P$1") (pintype "passive"))
      (node (ref "C54") (pin "P$2") (pinfunction "2_P$2") (pintype "passive"))
      (node (ref "C55") (pin "P$2") (pinfunction "2_P$2") (pintype "passive"))
      (node (ref "C56") (pin "P$2") (pinfunction "2_P$2") (pintype "passive"))
      (node (ref "C58") (pin "P$1") (pinfunction "1_P$1") (pintype "passive"))
      (node (ref "C59") (pin "P$1") (pinfunction "1_P$1") (pintype "passive"))
      (node (ref "C60") (pin "P$1") (pinfunction "1_P$1") (pintype "passive"))
      (node (ref "C61") (pin "P$2") (pinfunction "2_P$2") (pintype "passive"))
      (node (ref "C62") (pin "P$1") (pinfunction "1_P$1") (pintype "passive"))
      (node (ref "C63") (pin "P$1") (pinfunction "1_P$1") (pintype "passive"))
      (node (ref "FB2/2") (pin "1") (pinfunction "P$1_1") (pintype "bidirectional"))
      (node (ref "IC4") (pin "3") (pinfunction "OUT_3") (pintype "output"))
      (node (ref "J1") (pin "P$20") (pinfunction "P$20_P$20") (pintype "bidirectional"))
      (node (ref "J11") (pin "2") (pinfunction "2_2") (pintype "passive"))
      (node (ref "J11") (pin "4") (pinfunction "4_4") (pintype "passive"))
      (node (ref "J12") (pin "P$1") (pinfunction "3.3V_P$1") (pintype "power_in"))
      (node (ref "J12") (pin "P$17") (pinfunction "3.3V_P$17") (pintype "power_in"))
      (node (ref "R18") (pin "P$2") (pinfunction "2_P$2") (pintype "passive"))
      (node (ref "R23") (pin "P$2") (pinfunction "2_P$2") (pintype "passive"))
      (node (ref "R24") (pin "P$2") (pinfunction "2_P$2") (pintype "passive"))
      (node (ref "R26") (pin "P$2") (pinfunction "2_P$2") (pintype "passive"))
      (node (ref "R27") (pin "P$2") (pinfunction "2_P$2") (pintype "passive"))
      (node (ref "R28") (pin "P$2") (pinfunction "2_P$2") (pintype "passive"))
      (node (ref "R29") (pin "P$2") (pinfunction "2_P$2") (pintype "passive"))
      (node (ref "R8") (pin "P$1") (pinfunction "1_P$1") (pintype "passive"))
      (node (ref "U$2") (pin "P19") (pinfunction "VDD_P19") (pintype "bidirectional"))
      (node (ref "U3") (pin "14") (pinfunction "VDDIO_14") (pintype "power_in"))
      (node (ref "U4") (pin "110") (pinfunction "VCC(IO)5_110") (pintype "bidirectional"))
      (node (ref "U4") (pin "123") (pinfunction "VCC(IO)6_123") (pintype "bidirectional"))
      (node (ref "U4") (pin "138") (pinfunction "VCC(IO)7_138") (pintype "bidirectional"))
      (node (ref "U4") (pin "149") (pinfunction "VCC(IO)8_149") (pintype "bidirectional"))
      (node (ref "U4") (pin "154") (pinfunction "VREFH_154") (pintype "bidirectional"))
      (node (ref "U4") (pin "155") (pinfunction "AVCC0_155") (pintype "bidirectional"))
      (node (ref "U4") (pin "158") (pinfunction "VREFH0_158") (pintype "bidirectional"))
      (node (ref "U4") (pin "171") (pinfunction "VCC(IO)9_171") (pintype "bidirectional"))
      (node (ref "U4") (pin "25") (pinfunction "VCC1_25") (pintype "bidirectional"))
      (node (ref "U4") (pin "26") (pinfunction "AVCC_SUBHS_26") (pintype "bidirectional"))
      (node (ref "U4") (pin "34") (pinfunction "VCC_USBHS_34") (pintype "bidirectional"))
      (node (ref "U4") (pin "48") (pinfunction "VCC_USB_48") (pintype "bidirectional"))
      (node (ref "U4") (pin "61") (pinfunction "VCC(IO)2_61") (pintype "bidirectional"))
      (node (ref "U4") (pin "84") (pinfunction "VCC(IO)3_84") (pintype "bidirectional"))
      (node (ref "U4") (pin "97") (pinfunction "VCC(IO)4_97") (pintype "bidirectional"))
      (node (ref "U6") (pin "7") (pinfunction "+VS_7") (pintype "power_in"))
      (node (ref "U7") (pin "7") (pinfunction "+VS_7") (pintype "power_in"))
    )
    (net (code "170") (name "VDD5") (class "Default")
      (node (ref "C27") (pin "P$1") (pinfunction "1_P$1") (pintype "passive"))
      (node (ref "C28") (pin "1") (pinfunction "1_1") (pintype "passive"))
      (node (ref "C5") (pin "P$1") (pinfunction "1_P$1") (pintype "passive"))
      (node (ref "C8") (pin "P$1") (pinfunction "1_P$1") (pintype "passive"))
      (node (ref "IC3") (pin "3") (pinfunction "OUT_3") (pintype "output"))
      (node (ref "J12") (pin "P$2") (pinfunction "5V_P$2") (pintype "power_in"))
      (node (ref "J12") (pin "P$4") (pinfunction "5V_P$4") (pintype "power_in"))
      (node (ref "R1") (pin "P$2") (pinfunction "2_P$2") (pintype "passive"))
      (node (ref "R12") (pin "P$2") (pinfunction "2_P$2") (pintype "passive"))
      (node (ref "R9") (pin "P$1") (pinfunction "1_P$1") (pintype "passive"))
      (node (ref "U2") (pin "4") (pinfunction "VIN_4") (pintype "input"))
    )
    (net (code "171") (name "VDD_1.2") (class "Default")
      (node (ref "C45") (pin "P$1") (pinfunction "1_P$1") (pintype "passive"))
      (node (ref "C46") (pin "P$1") (pinfunction "1_P$1") (pintype "passive"))
      (node (ref "U3") (pin "1") (pinfunction "VDD_1.2_1") (pintype "power_in"))
    )
    (net (code "172") (name "WARNOUT") (class "Default")
      (node (ref "U$2") (pin "P9") (pinfunction "WARNOUT_P9") (pintype "bidirectional"))
      (node (ref "U4") (pin "128") (pinfunction "P1_4_128") (pintype "bidirectional"))
    )
    (net (code "173") (name "XCIN") (class "Default")
      (node (ref "C50") (pin "P$1") (pinfunction "1_P$1") (pintype "passive"))
      (node (ref "U4") (pin "20") (pinfunction "XCIN_20") (pintype "bidirectional"))
      (node (ref "X3") (pin "P$1") (pinfunction "P$1_P$1") (pintype "bidirectional"))
    )
    (net (code "174") (name "XCOUT") (class "Default")
      (node (ref "C51") (pin "P$1") (pinfunction "1_P$1") (pintype "passive"))
      (node (ref "U4") (pin "21") (pinfunction "XCOUT_21") (pintype "bidirectional"))
      (node (ref "X3") (pin "P$2") (pinfunction "P$2_P$2") (pintype "bidirectional"))
    )
    (net (code "175") (name "XII") (class "Default")
      (node (ref "C42") (pin "P$1") (pinfunction "1_P$1") (pintype "passive"))
      (node (ref "U$3") (pin "1") (pinfunction "1_1") (pintype "bidirectional"))
      (node (ref "U3") (pin "8") (pinfunction "XI_8") (pintype "input"))
    )
    (net (code "176") (name "XOO") (class "Default")
      (node (ref "C41") (pin "P$1") (pinfunction "1_P$1") (pintype "passive"))
      (node (ref "U$3") (pin "3") (pinfunction "3_3") (pintype "bidirectional"))
      (node (ref "U3") (pin "7") (pinfunction "XO_7") (pintype "output"))
    )
    (net (code "177") (name "XTAL1") (class "Default")
      (node (ref "C52") (pin "P$1") (pinfunction "1_P$1") (pintype "passive"))
      (node (ref "U4") (pin "23") (pinfunction "P2_13/XTAL_23") (pintype "bidirectional"))
      (node (ref "X4") (pin "1") (pinfunction "1_1") (pintype "bidirectional"))
    )
    (net (code "178") (name "XTAL2") (class "Default")
      (node (ref "C53") (pin "P$1") (pinfunction "1_P$1") (pintype "passive"))
      (node (ref "U4") (pin "24") (pinfunction "P2_12/EXTAL_24") (pintype "bidirectional"))
      (node (ref "X4") (pin "3") (pinfunction "3_3") (pintype "bidirectional"))
    )
    (net (code "179") (name "ZX0") (class "Default")
      (node (ref "U$2") (pin "P2") (pinfunction "ZX0_P2") (pintype "bidirectional"))
      (node (ref "U4") (pin "135") (pinfunction "P8_2_135") (pintype "bidirectional"))
    )
    (net (code "180") (name "ZX1") (class "Default")
      (node (ref "U$2") (pin "P3") (pinfunction "ZX1_P3") (pintype "bidirectional"))
      (node (ref "U4") (pin "134") (pinfunction "P8_1_134") (pintype "bidirectional"))
    )
    (net (code "181") (name "ZX2") (class "Default")
      (node (ref "U$2") (pin "P4") (pinfunction "ZX2_P4") (pintype "bidirectional"))
      (node (ref "U4") (pin "133") (pinfunction "P8_0_133") (pintype "bidirectional"))
    )
    (net (code "182") (name "unconnected-(U4-VBAT-Pad18)") (class "Default")
      (node (ref "U4") (pin "18") (pinfunction "VBAT_18") (pintype "bidirectional"))
    )
    (net (code "183") (name "unconnected-(U5-NC1-PadP$1)") (class "Default")
      (node (ref "U5") (pin "P$1") (pinfunction "NC1_P$1") (pintype "bidirectional"))
    )
    (net (code "184") (name "unconnected-(U5-NC2-PadP$4)") (class "Default")
      (node (ref "U5") (pin "P$4") (pinfunction "NC2_P$4") (pintype "bidirectional"))
    )
    (net (code "185") (name "unconnected-(U5-NC3-PadP$7)") (class "Default")
      (node (ref "U5") (pin "P$7") (pinfunction "NC3_P$7") (pintype "bidirectional"))
    )
    (net (code "186") (name "unconnected-(U6-NC-Pad4)") (class "Default")
      (node (ref "U6") (pin "4") (pinfunction "NC_4") (pintype "no_connect"))
    )
    (net (code "187") (name "unconnected-(U7-NC-Pad4)") (class "Default")
      (node (ref "U7") (pin "4") (pinfunction "NC_4") (pintype "no_connect"))
    )
  )
)
